# eightbyeight.net
KiCad netlist of a schematic drawn in EAGLE
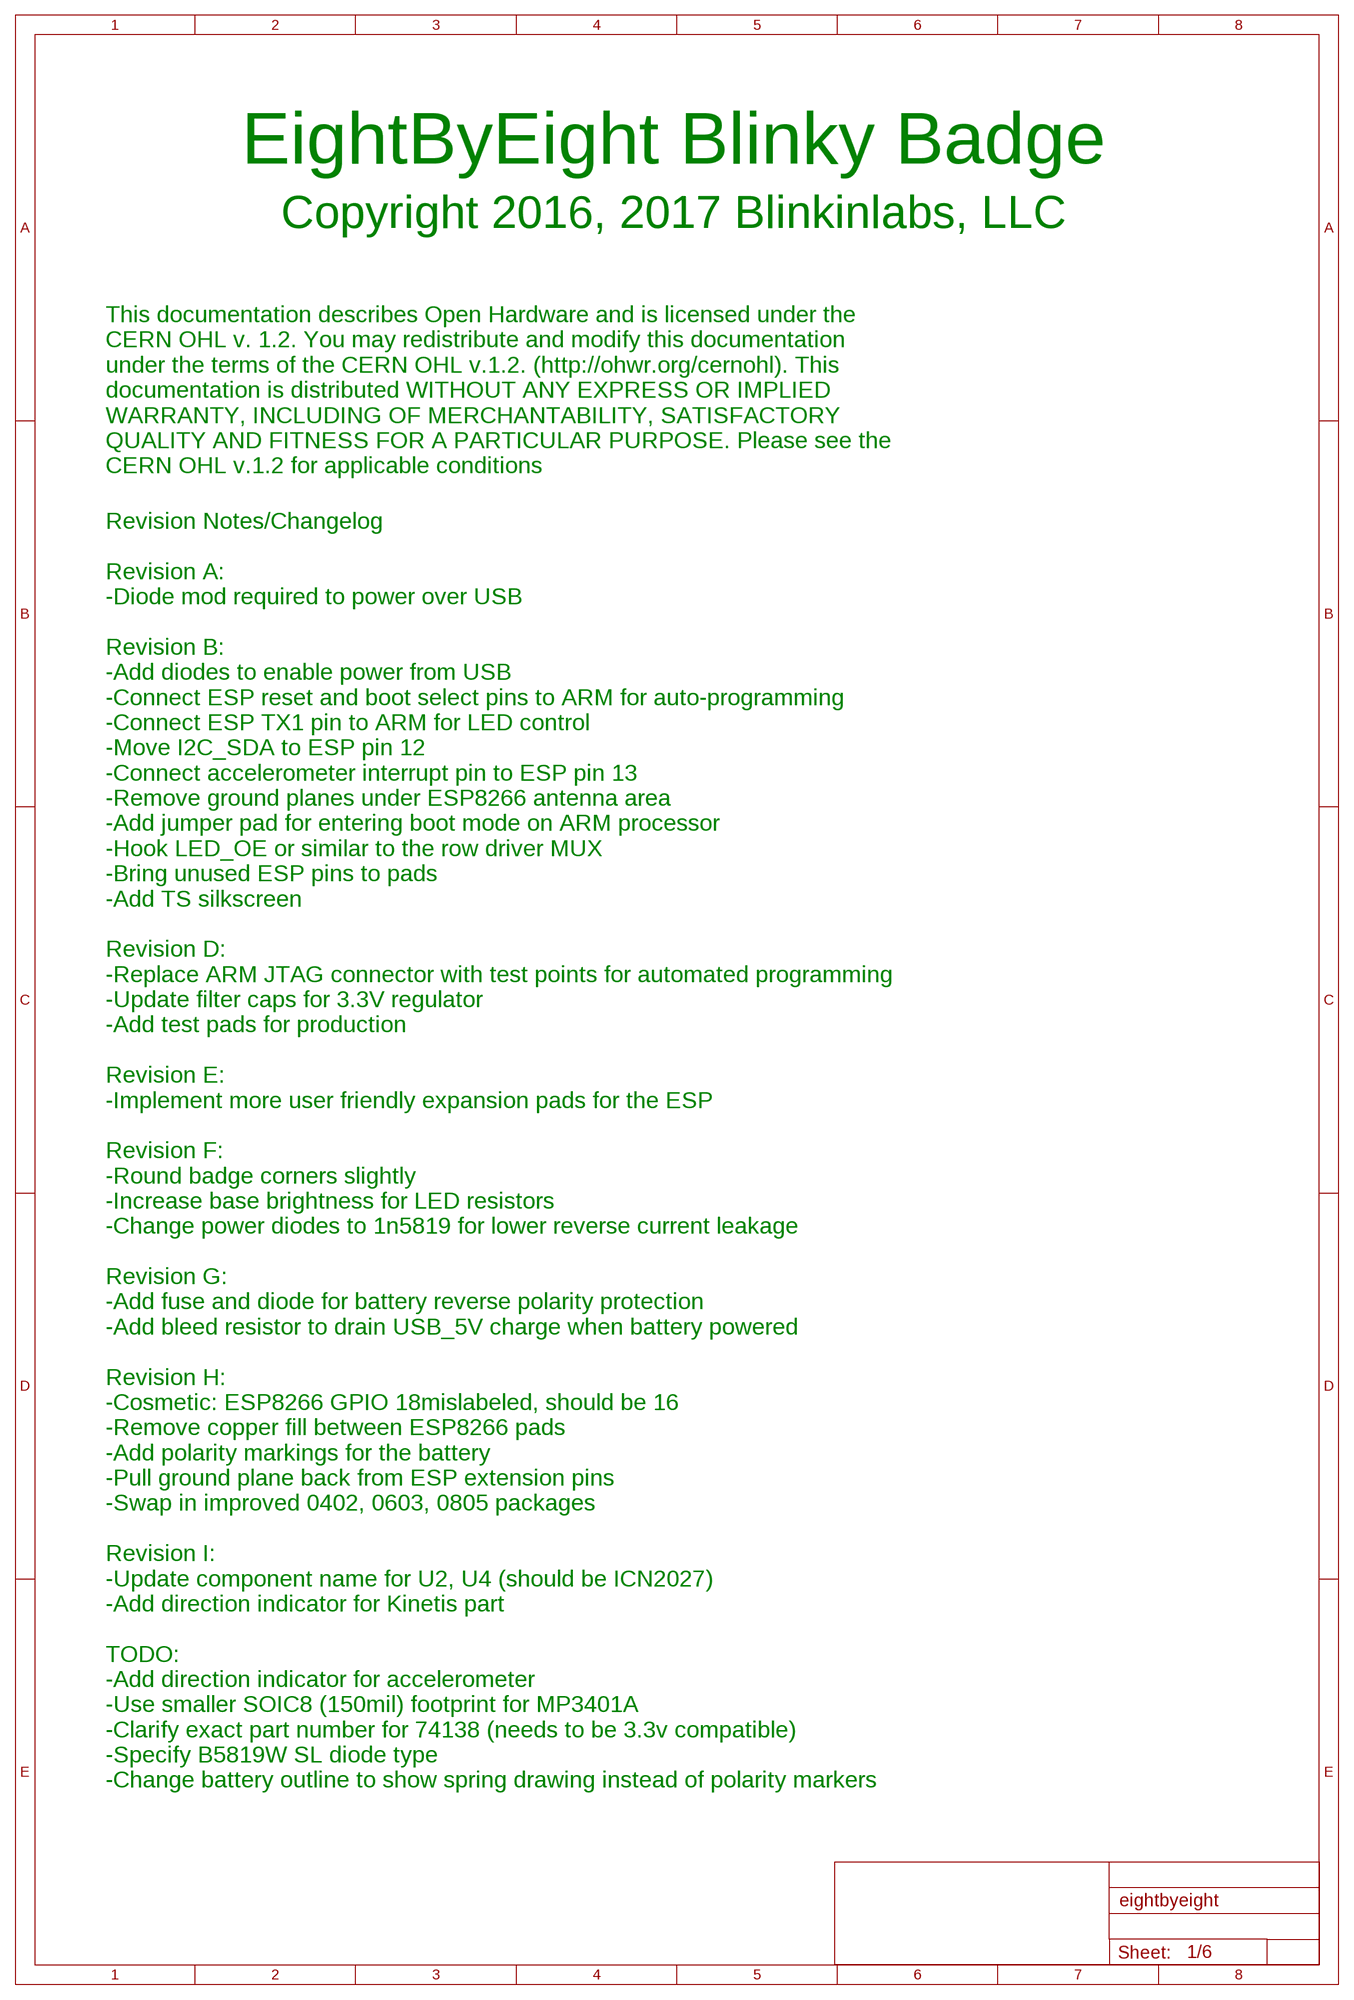
[diagram p0: schematic, sheet 1]
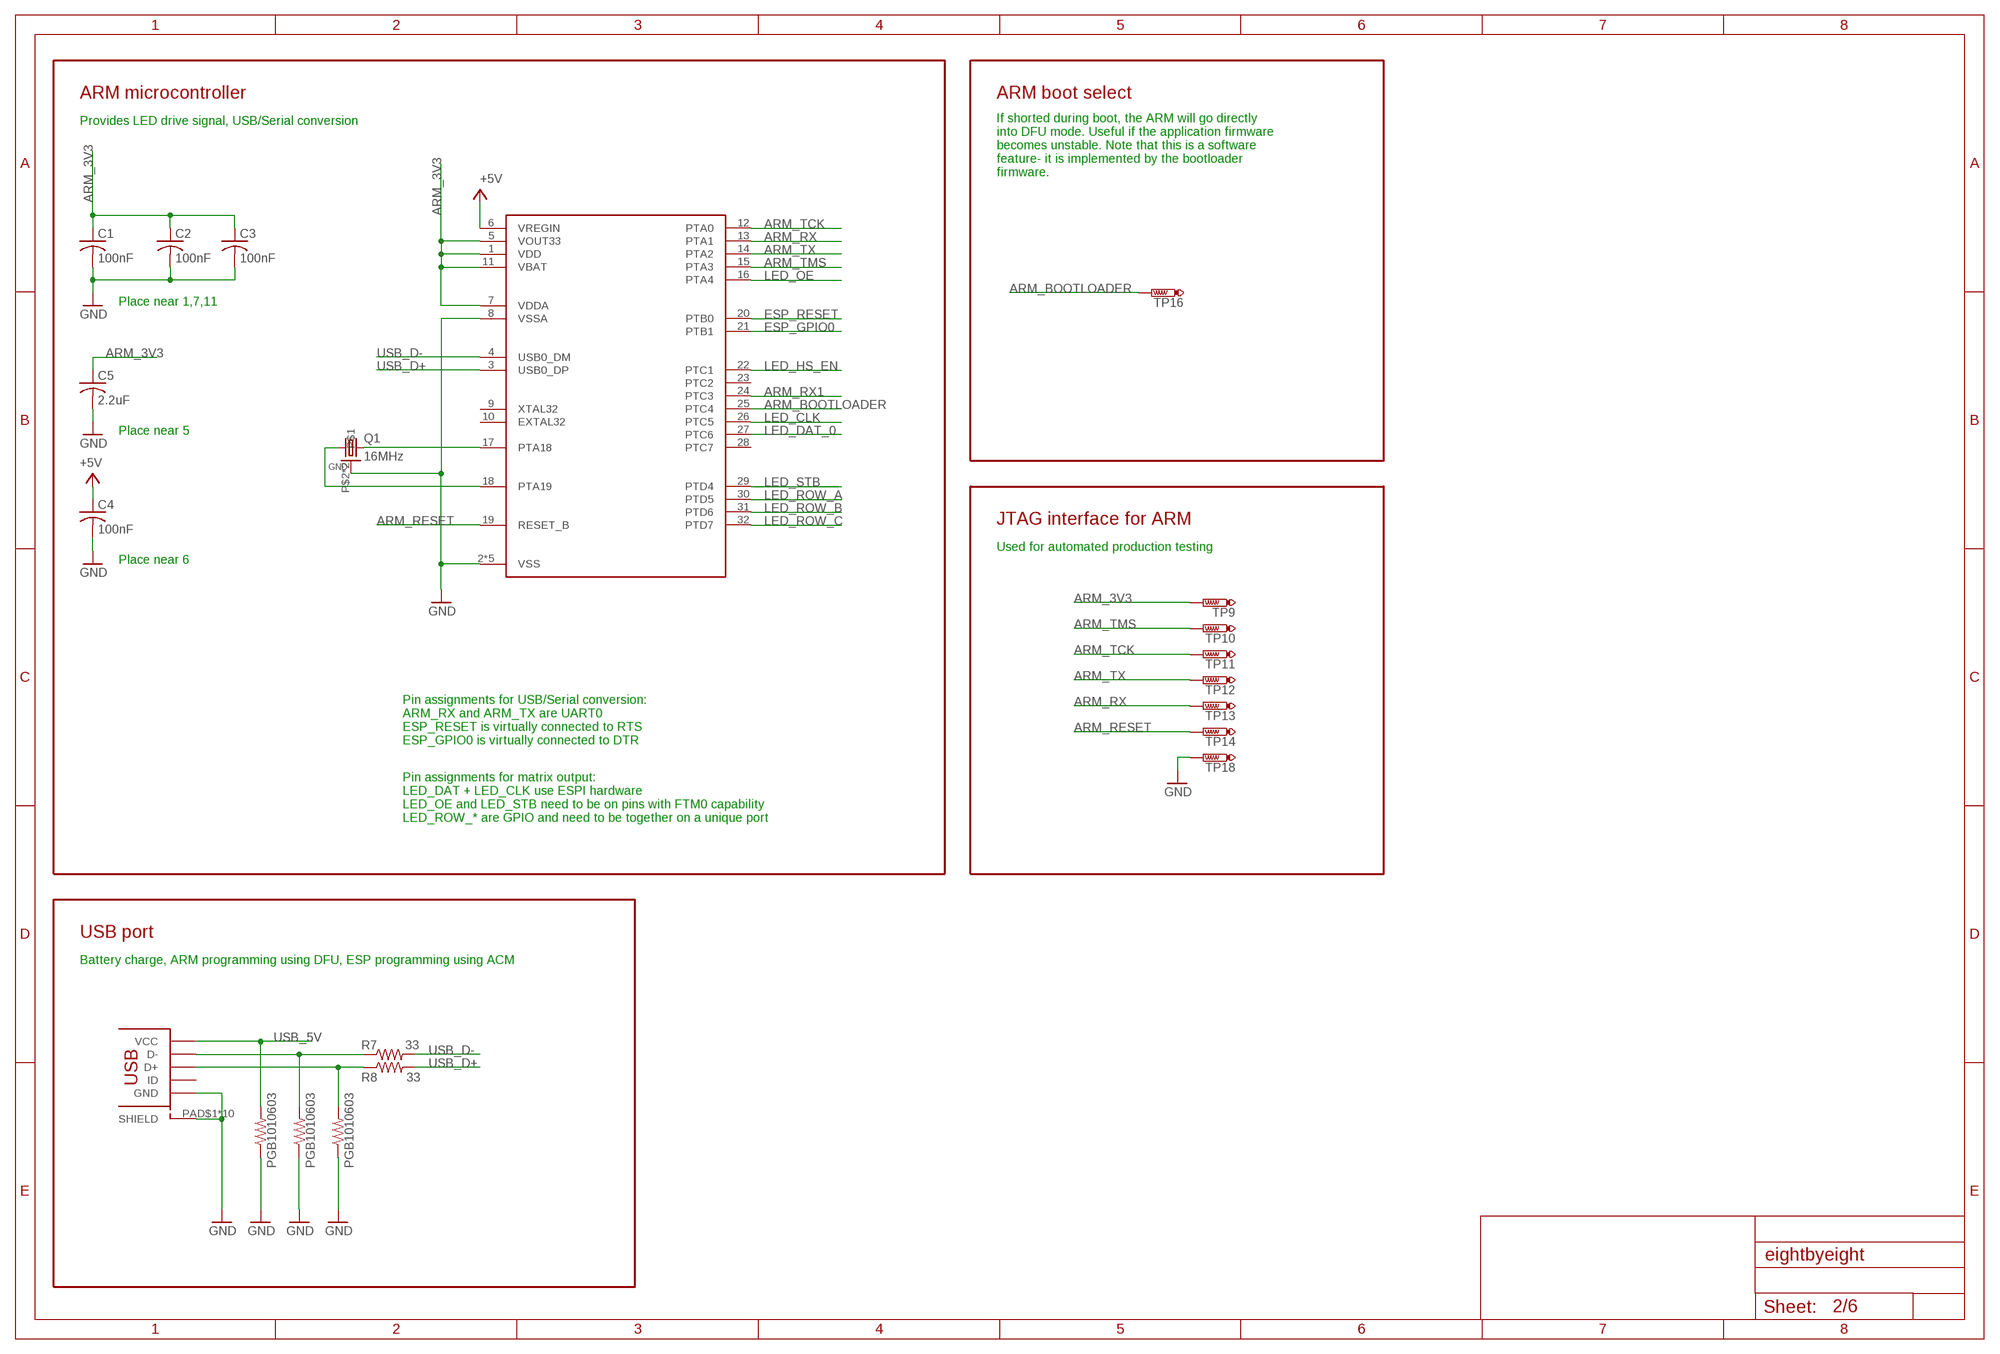
[diagram p1: schematic, sheet 2]
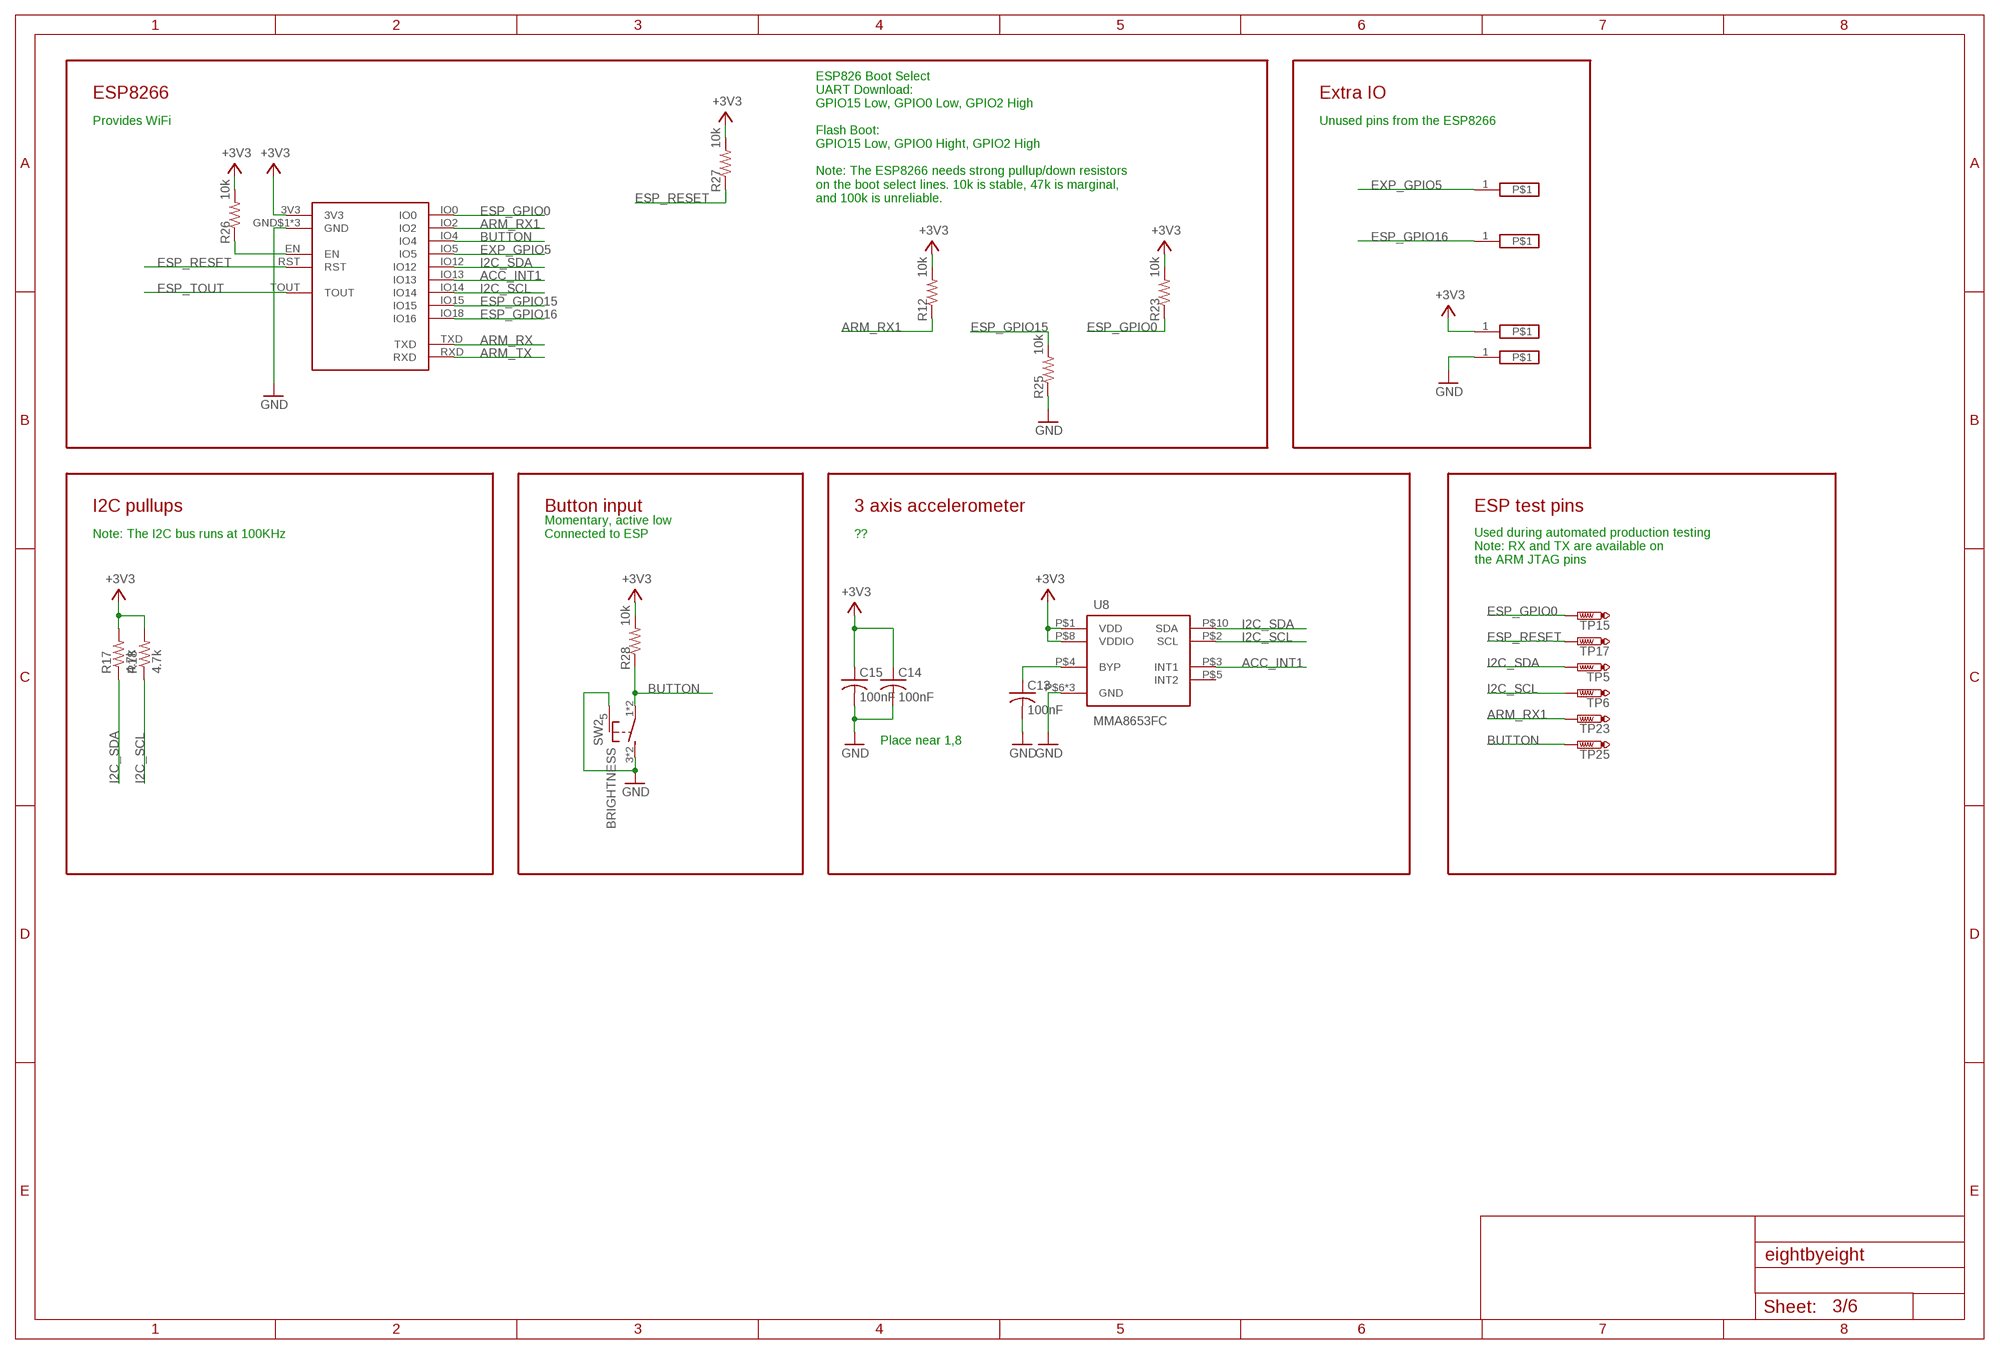
[diagram p2: schematic, sheet 3]
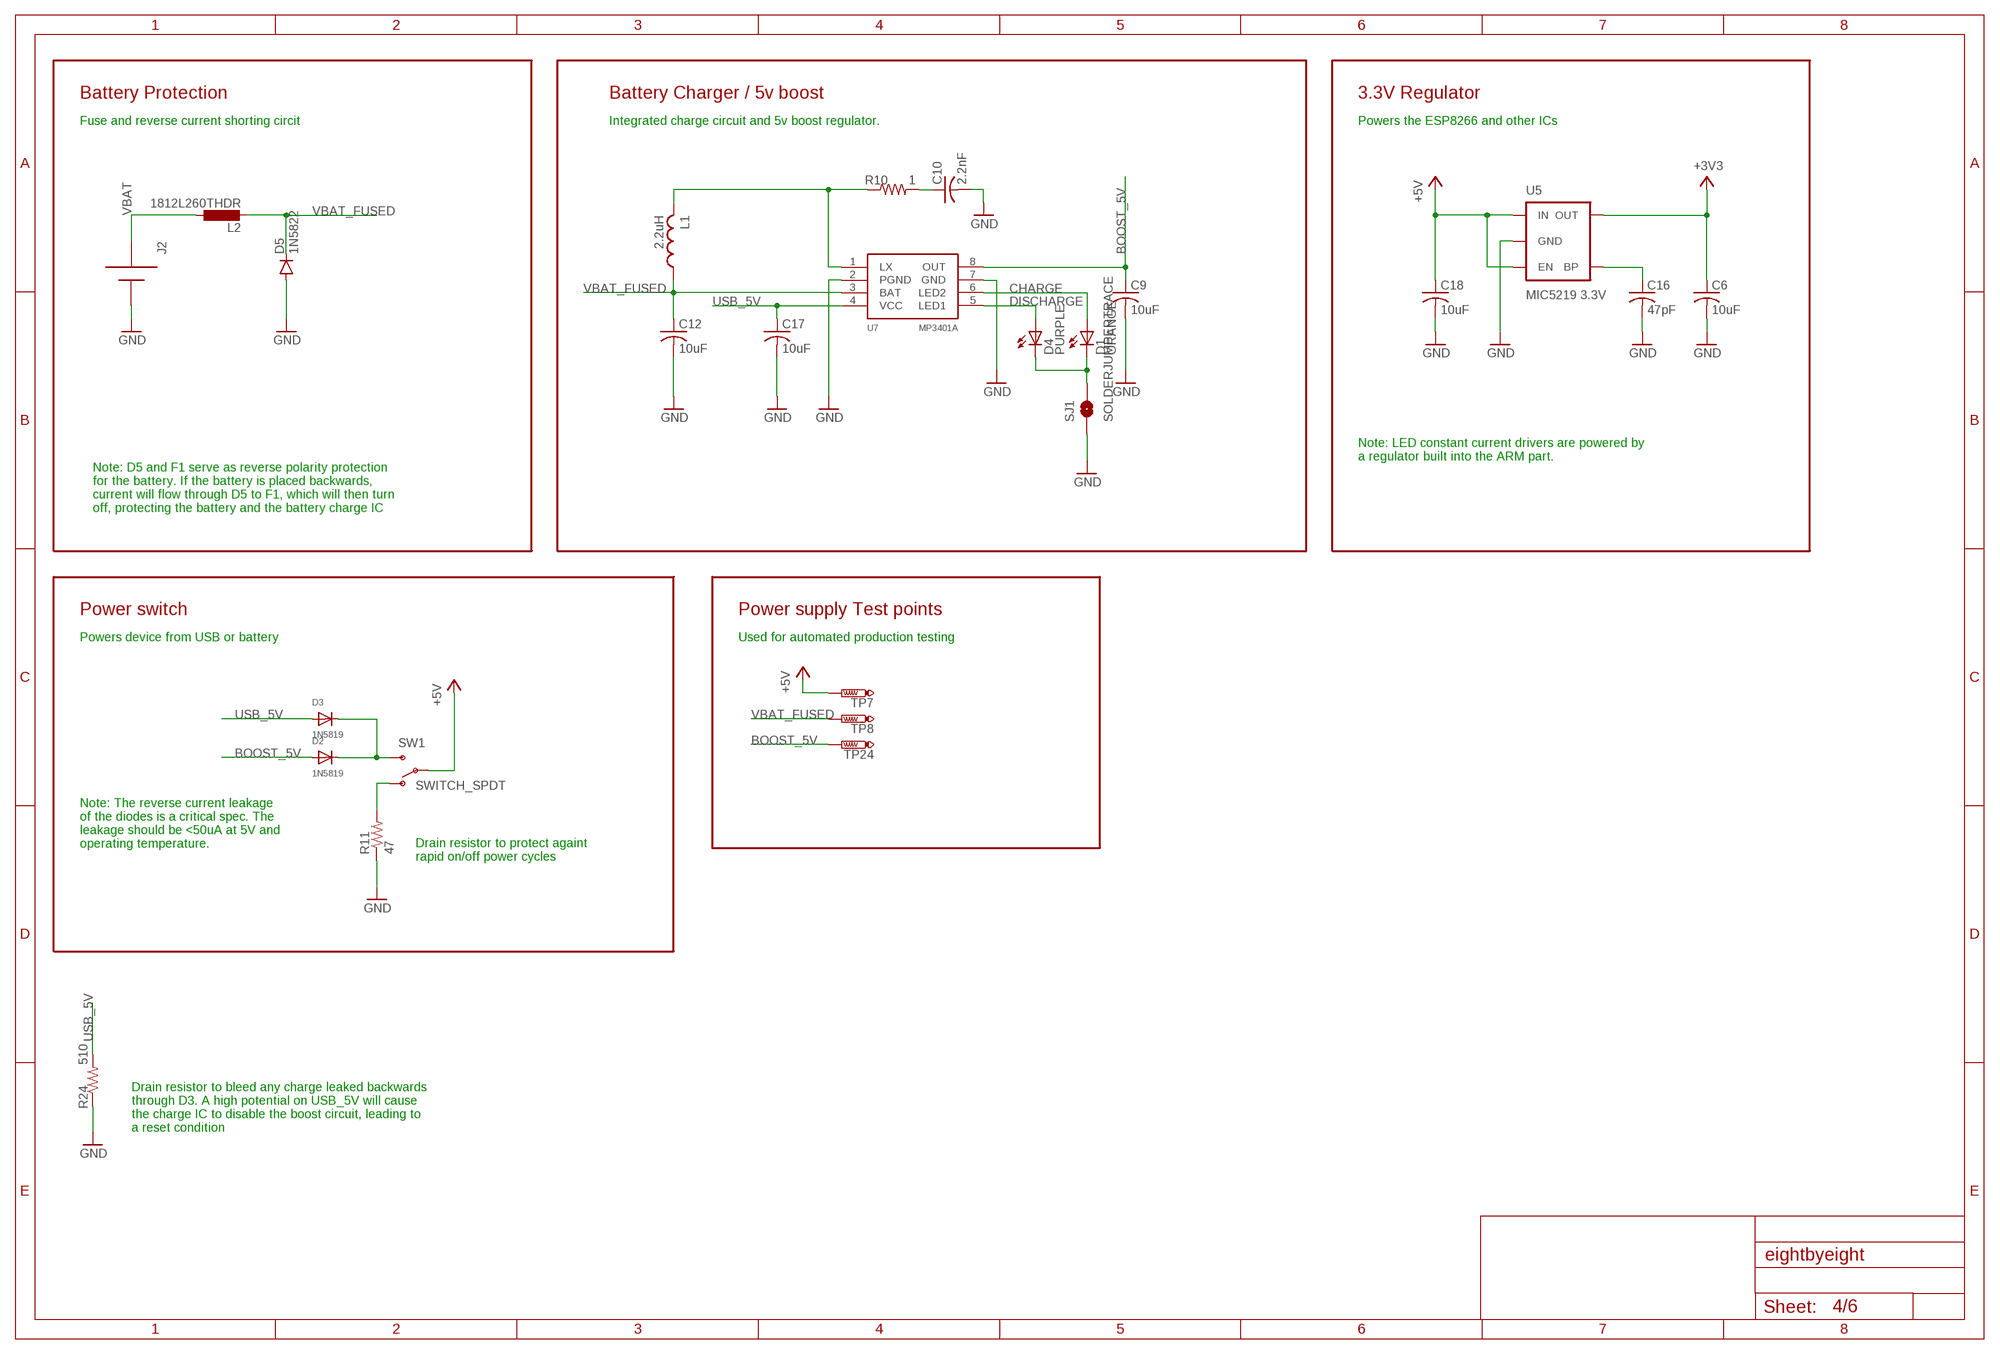
[diagram p3: schematic, sheet 4]
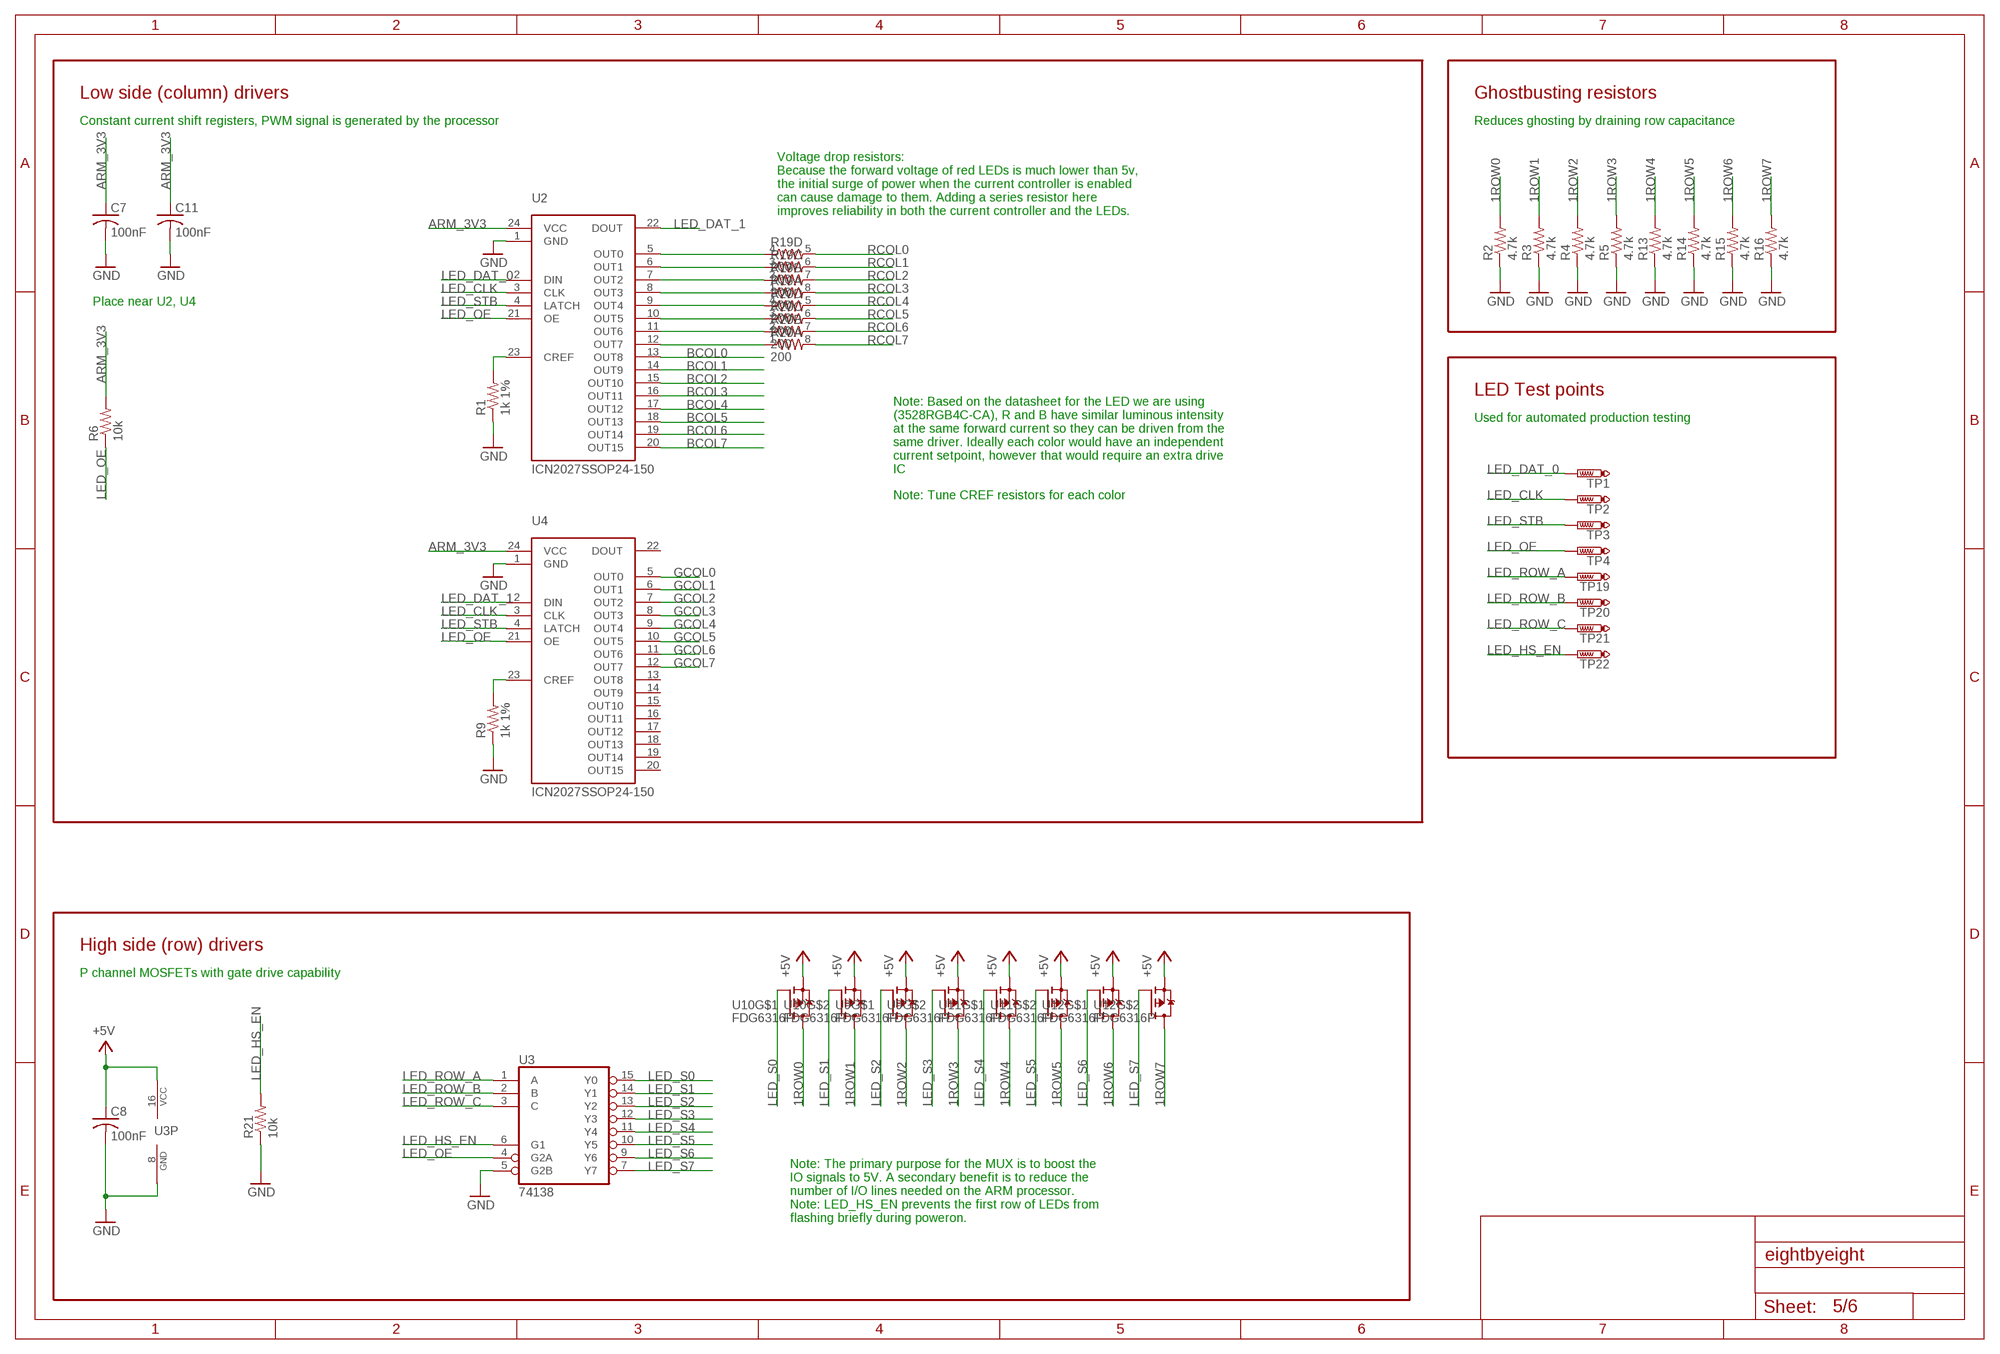
[diagram p4: schematic, sheet 5]
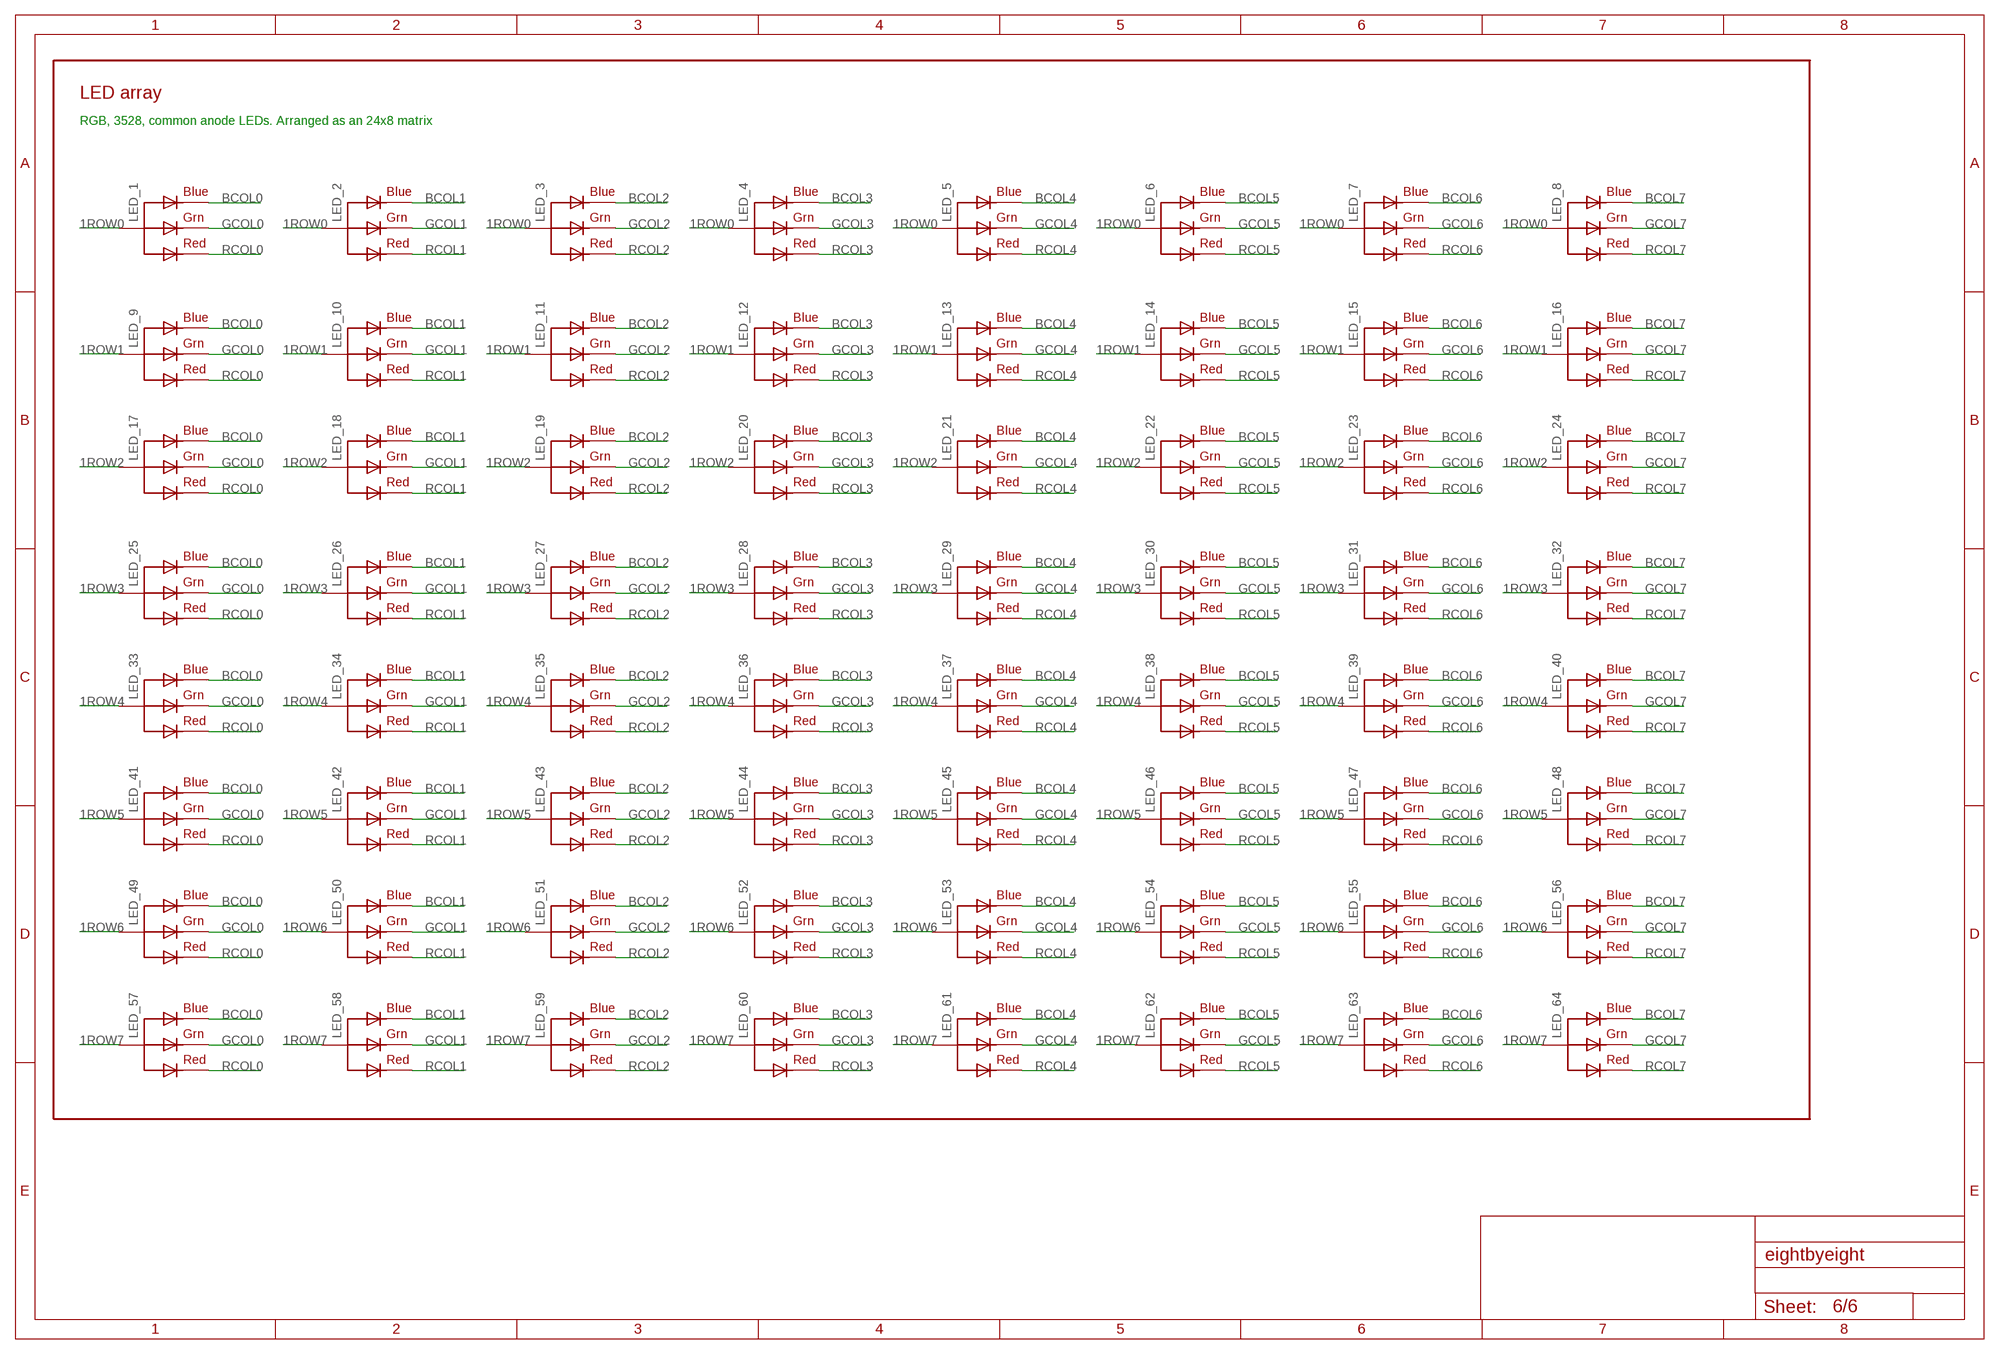
[diagram p5: schematic, sheet 6]

(export (version "E")
  (design (tool "Eeschema 10.0.6"))
  (components
    (comp (ref "C7")
      (value "100nF")
      (footprint "eagle-import:CAP_0402")
      (libsource (lib "eagle-import") (part "C_US0402"))
    )
    (comp (ref "C8")
      (value "100nF")
      (footprint "eagle-import:CAP_0402")
      (libsource (lib "eagle-import") (part "C_US0402"))
    )
    (comp (ref "C11")
      (value "100nF")
      (footprint "eagle-import:CAP_0402")
      (libsource (lib "eagle-import") (part "C_US0402"))
    )
    (comp (ref "R1")
      (value "1k 1%")
      (footprint "eagle-import:R_0402")
      (libsource (lib "eagle-import") (part "R_US0402"))
    )
    (comp (ref "R2")
      (value "4.7k")
      (footprint "eagle-import:R_0402")
      (libsource (lib "eagle-import") (part "R_US0402"))
    )
    (comp (ref "R3")
      (value "4.7k")
      (footprint "eagle-import:R_0402")
      (libsource (lib "eagle-import") (part "R_US0402"))
    )
    (comp (ref "R4")
      (value "4.7k")
      (footprint "eagle-import:R_0402")
      (libsource (lib "eagle-import") (part "R_US0402"))
    )
    (comp (ref "R5")
      (value "4.7k")
      (footprint "eagle-import:R_0402")
      (libsource (lib "eagle-import") (part "R_US0402"))
    )
    (comp (ref "R6")
      (value "10k")
      (footprint "eagle-import:R_0402")
      (libsource (lib "eagle-import") (part "R_US0402"))
    )
    (comp (ref "R9")
      (value "1k 1%")
      (footprint "eagle-import:R_0402")
      (libsource (lib "eagle-import") (part "R_US0402"))
    )
    (comp (ref "R13")
      (value "4.7k")
      (footprint "eagle-import:R_0402")
      (libsource (lib "eagle-import") (part "R_US0402"))
    )
    (comp (ref "R14")
      (value "4.7k")
      (footprint "eagle-import:R_0402")
      (libsource (lib "eagle-import") (part "R_US0402"))
    )
    (comp (ref "R15")
      (value "4.7k")
      (footprint "eagle-import:R_0402")
      (libsource (lib "eagle-import") (part "R_US0402"))
    )
    (comp (ref "R16")
      (value "4.7k")
      (footprint "eagle-import:R_0402")
      (libsource (lib "eagle-import") (part "R_US0402"))
    )
    (comp (ref "R19")
      (value "200")
      (footprint "eagle-import:0603-ARV")
      (libsource (lib "eagle-import") (part "RESISTOR-ARRAY0603-ARV"))
    )
    (comp (ref "R20")
      (value "200")
      (footprint "eagle-import:0603-ARV")
      (libsource (lib "eagle-import") (part "RESISTOR-ARRAY0603-ARV"))
    )
    (comp (ref "R21")
      (value "10k")
      (footprint "eagle-import:R_0402")
      (libsource (lib "eagle-import") (part "R_US0402"))
    )
    (comp (ref "TP1")
      (value "PTR1B1,27")
      (footprint "eagle-import:B1,27")
      (libsource (lib "eagle-import") (part "PTR1B1,27"))
    )
    (comp (ref "TP2")
      (value "PTR1B1,27")
      (footprint "eagle-import:B1,27")
      (libsource (lib "eagle-import") (part "PTR1B1,27"))
    )
    (comp (ref "TP3")
      (value "PTR1B1,27")
      (footprint "eagle-import:B1,27")
      (libsource (lib "eagle-import") (part "PTR1B1,27"))
    )
    (comp (ref "TP4")
      (value "PTR1B1,27")
      (footprint "eagle-import:B1,27")
      (libsource (lib "eagle-import") (part "PTR1B1,27"))
    )
    (comp (ref "TP19")
      (value "PTR1B1,27")
      (footprint "eagle-import:B1,27")
      (libsource (lib "eagle-import") (part "PTR1B1,27"))
    )
    (comp (ref "TP20")
      (value "PTR1B1,27")
      (footprint "eagle-import:B1,27")
      (libsource (lib "eagle-import") (part "PTR1B1,27"))
    )
    (comp (ref "TP21")
      (value "PTR1B1,27")
      (footprint "eagle-import:B1,27")
      (libsource (lib "eagle-import") (part "PTR1B1,27"))
    )
    (comp (ref "TP22")
      (value "PTR1B1,27")
      (footprint "eagle-import:B1,27")
      (libsource (lib "eagle-import") (part "PTR1B1,27"))
    )
    (comp (ref "U2")
      (value "ICN2027SSOP24-150")
      (footprint "eagle-import:SSOP24-150")
      (libsource (lib "eagle-import") (part "ICN2027SSOP24-150"))
    )
    (comp (ref "U3")
      (value "74138")
      (footprint "eagle-import:TSSOP16")
      (libsource (lib "eagle-import") (part "74138"))
    )
    (comp (ref "U4")
      (value "ICN2027SSOP24-150")
      (footprint "eagle-import:SSOP24-150")
      (libsource (lib "eagle-import") (part "ICN2027SSOP24-150"))
    )
    (comp (ref "U9")
      (value "FDG6316P")
      (footprint "eagle-import:SC70-6L")
      (libsource (lib "eagle-import") (part "FDG6316P"))
    )
    (comp (ref "U10")
      (value "FDG6316P")
      (footprint "eagle-import:SC70-6L")
      (libsource (lib "eagle-import") (part "FDG6316P"))
    )
    (comp (ref "U11")
      (value "FDG6316P")
      (footprint "eagle-import:SC70-6L")
      (libsource (lib "eagle-import") (part "FDG6316P"))
    )
    (comp (ref "U12")
      (value "FDG6316P")
      (footprint "eagle-import:SC70-6L")
      (libsource (lib "eagle-import") (part "FDG6316P"))
    )
    (comp (ref "LED_1")
      (value "LED_RGB_CA3528")
      (footprint "eagle-import:LED_3528")
      (libsource (lib "eagle-import") (part "LED_RGB_CA3528"))
    )
    (comp (ref "LED_2")
      (value "LED_RGB_CA3528")
      (footprint "eagle-import:LED_3528")
      (libsource (lib "eagle-import") (part "LED_RGB_CA3528"))
    )
    (comp (ref "LED_3")
      (value "LED_RGB_CA3528")
      (footprint "eagle-import:LED_3528")
      (libsource (lib "eagle-import") (part "LED_RGB_CA3528"))
    )
    (comp (ref "LED_4")
      (value "LED_RGB_CA3528")
      (footprint "eagle-import:LED_3528")
      (libsource (lib "eagle-import") (part "LED_RGB_CA3528"))
    )
    (comp (ref "LED_5")
      (value "LED_RGB_CA3528")
      (footprint "eagle-import:LED_3528")
      (libsource (lib "eagle-import") (part "LED_RGB_CA3528"))
    )
    (comp (ref "LED_6")
      (value "LED_RGB_CA3528")
      (footprint "eagle-import:LED_3528")
      (libsource (lib "eagle-import") (part "LED_RGB_CA3528"))
    )
    (comp (ref "LED_7")
      (value "LED_RGB_CA3528")
      (footprint "eagle-import:LED_3528")
      (libsource (lib "eagle-import") (part "LED_RGB_CA3528"))
    )
    (comp (ref "LED_8")
      (value "LED_RGB_CA3528")
      (footprint "eagle-import:LED_3528")
      (libsource (lib "eagle-import") (part "LED_RGB_CA3528"))
    )
    (comp (ref "LED_9")
      (value "LED_RGB_CA3528")
      (footprint "eagle-import:LED_3528")
      (libsource (lib "eagle-import") (part "LED_RGB_CA3528"))
    )
    (comp (ref "LED_10")
      (value "LED_RGB_CA3528")
      (footprint "eagle-import:LED_3528")
      (libsource (lib "eagle-import") (part "LED_RGB_CA3528"))
    )
    (comp (ref "LED_11")
      (value "LED_RGB_CA3528")
      (footprint "eagle-import:LED_3528")
      (libsource (lib "eagle-import") (part "LED_RGB_CA3528"))
    )
    (comp (ref "LED_12")
      (value "LED_RGB_CA3528")
      (footprint "eagle-import:LED_3528")
      (libsource (lib "eagle-import") (part "LED_RGB_CA3528"))
    )
    (comp (ref "LED_13")
      (value "LED_RGB_CA3528")
      (footprint "eagle-import:LED_3528")
      (libsource (lib "eagle-import") (part "LED_RGB_CA3528"))
    )
    (comp (ref "LED_14")
      (value "LED_RGB_CA3528")
      (footprint "eagle-import:LED_3528")
      (libsource (lib "eagle-import") (part "LED_RGB_CA3528"))
    )
    (comp (ref "LED_15")
      (value "LED_RGB_CA3528")
      (footprint "eagle-import:LED_3528")
      (libsource (lib "eagle-import") (part "LED_RGB_CA3528"))
    )
    (comp (ref "LED_16")
      (value "LED_RGB_CA3528")
      (footprint "eagle-import:LED_3528")
      (libsource (lib "eagle-import") (part "LED_RGB_CA3528"))
    )
    (comp (ref "LED_17")
      (value "LED_RGB_CA3528")
      (footprint "eagle-import:LED_3528")
      (libsource (lib "eagle-import") (part "LED_RGB_CA3528"))
    )
    (comp (ref "LED_18")
      (value "LED_RGB_CA3528")
      (footprint "eagle-import:LED_3528")
      (libsource (lib "eagle-import") (part "LED_RGB_CA3528"))
    )
    (comp (ref "LED_19")
      (value "LED_RGB_CA3528")
      (footprint "eagle-import:LED_3528")
      (libsource (lib "eagle-import") (part "LED_RGB_CA3528"))
    )
    (comp (ref "LED_20")
      (value "LED_RGB_CA3528")
      (footprint "eagle-import:LED_3528")
      (libsource (lib "eagle-import") (part "LED_RGB_CA3528"))
    )
    (comp (ref "LED_21")
      (value "LED_RGB_CA3528")
      (footprint "eagle-import:LED_3528")
      (libsource (lib "eagle-import") (part "LED_RGB_CA3528"))
    )
    (comp (ref "LED_22")
      (value "LED_RGB_CA3528")
      (footprint "eagle-import:LED_3528")
      (libsource (lib "eagle-import") (part "LED_RGB_CA3528"))
    )
    (comp (ref "LED_23")
      (value "LED_RGB_CA3528")
      (footprint "eagle-import:LED_3528")
      (libsource (lib "eagle-import") (part "LED_RGB_CA3528"))
    )
    (comp (ref "LED_24")
      (value "LED_RGB_CA3528")
      (footprint "eagle-import:LED_3528")
      (libsource (lib "eagle-import") (part "LED_RGB_CA3528"))
    )
    (comp (ref "LED_25")
      (value "LED_RGB_CA3528")
      (footprint "eagle-import:LED_3528")
      (libsource (lib "eagle-import") (part "LED_RGB_CA3528"))
    )
    (comp (ref "LED_26")
      (value "LED_RGB_CA3528")
      (footprint "eagle-import:LED_3528")
      (libsource (lib "eagle-import") (part "LED_RGB_CA3528"))
    )
    (comp (ref "LED_27")
      (value "LED_RGB_CA3528")
      (footprint "eagle-import:LED_3528")
      (libsource (lib "eagle-import") (part "LED_RGB_CA3528"))
    )
    (comp (ref "LED_28")
      (value "LED_RGB_CA3528")
      (footprint "eagle-import:LED_3528")
      (libsource (lib "eagle-import") (part "LED_RGB_CA3528"))
    )
    (comp (ref "LED_29")
      (value "LED_RGB_CA3528")
      (footprint "eagle-import:LED_3528")
      (libsource (lib "eagle-import") (part "LED_RGB_CA3528"))
    )
    (comp (ref "LED_30")
      (value "LED_RGB_CA3528")
      (footprint "eagle-import:LED_3528")
      (libsource (lib "eagle-import") (part "LED_RGB_CA3528"))
    )
    (comp (ref "LED_31")
      (value "LED_RGB_CA3528")
      (footprint "eagle-import:LED_3528")
      (libsource (lib "eagle-import") (part "LED_RGB_CA3528"))
    )
    (comp (ref "LED_32")
      (value "LED_RGB_CA3528")
      (footprint "eagle-import:LED_3528")
      (libsource (lib "eagle-import") (part "LED_RGB_CA3528"))
    )
    (comp (ref "LED_33")
      (value "LED_RGB_CA3528")
      (footprint "eagle-import:LED_3528")
      (libsource (lib "eagle-import") (part "LED_RGB_CA3528"))
    )
    (comp (ref "LED_34")
      (value "LED_RGB_CA3528")
      (footprint "eagle-import:LED_3528")
      (libsource (lib "eagle-import") (part "LED_RGB_CA3528"))
    )
    (comp (ref "LED_35")
      (value "LED_RGB_CA3528")
      (footprint "eagle-import:LED_3528")
      (libsource (lib "eagle-import") (part "LED_RGB_CA3528"))
    )
    (comp (ref "LED_36")
      (value "LED_RGB_CA3528")
      (footprint "eagle-import:LED_3528")
      (libsource (lib "eagle-import") (part "LED_RGB_CA3528"))
    )
    (comp (ref "LED_37")
      (value "LED_RGB_CA3528")
      (footprint "eagle-import:LED_3528")
      (libsource (lib "eagle-import") (part "LED_RGB_CA3528"))
    )
    (comp (ref "LED_38")
      (value "LED_RGB_CA3528")
      (footprint "eagle-import:LED_3528")
      (libsource (lib "eagle-import") (part "LED_RGB_CA3528"))
    )
    (comp (ref "LED_39")
      (value "LED_RGB_CA3528")
      (footprint "eagle-import:LED_3528")
      (libsource (lib "eagle-import") (part "LED_RGB_CA3528"))
    )
    (comp (ref "LED_40")
      (value "LED_RGB_CA3528")
      (footprint "eagle-import:LED_3528")
      (libsource (lib "eagle-import") (part "LED_RGB_CA3528"))
    )
    (comp (ref "LED_41")
      (value "LED_RGB_CA3528")
      (footprint "eagle-import:LED_3528")
      (libsource (lib "eagle-import") (part "LED_RGB_CA3528"))
    )
    (comp (ref "LED_42")
      (value "LED_RGB_CA3528")
      (footprint "eagle-import:LED_3528")
      (libsource (lib "eagle-import") (part "LED_RGB_CA3528"))
    )
    (comp (ref "LED_43")
      (value "LED_RGB_CA3528")
      (footprint "eagle-import:LED_3528")
      (libsource (lib "eagle-import") (part "LED_RGB_CA3528"))
    )
    (comp (ref "LED_44")
      (value "LED_RGB_CA3528")
      (footprint "eagle-import:LED_3528")
      (libsource (lib "eagle-import") (part "LED_RGB_CA3528"))
    )
    (comp (ref "LED_45")
      (value "LED_RGB_CA3528")
      (footprint "eagle-import:LED_3528")
      (libsource (lib "eagle-import") (part "LED_RGB_CA3528"))
    )
    (comp (ref "LED_46")
      (value "LED_RGB_CA3528")
      (footprint "eagle-import:LED_3528")
      (libsource (lib "eagle-import") (part "LED_RGB_CA3528"))
    )
    (comp (ref "LED_47")
      (value "LED_RGB_CA3528")
      (footprint "eagle-import:LED_3528")
      (libsource (lib "eagle-import") (part "LED_RGB_CA3528"))
    )
    (comp (ref "LED_48")
      (value "LED_RGB_CA3528")
      (footprint "eagle-import:LED_3528")
      (libsource (lib "eagle-import") (part "LED_RGB_CA3528"))
    )
    (comp (ref "LED_49")
      (value "LED_RGB_CA3528")
      (footprint "eagle-import:LED_3528")
      (libsource (lib "eagle-import") (part "LED_RGB_CA3528"))
    )
    (comp (ref "LED_50")
      (value "LED_RGB_CA3528")
      (footprint "eagle-import:LED_3528")
      (libsource (lib "eagle-import") (part "LED_RGB_CA3528"))
    )
    (comp (ref "LED_51")
      (value "LED_RGB_CA3528")
      (footprint "eagle-import:LED_3528")
      (libsource (lib "eagle-import") (part "LED_RGB_CA3528"))
    )
    (comp (ref "LED_52")
      (value "LED_RGB_CA3528")
      (footprint "eagle-import:LED_3528")
      (libsource (lib "eagle-import") (part "LED_RGB_CA3528"))
    )
    (comp (ref "LED_53")
      (value "LED_RGB_CA3528")
      (footprint "eagle-import:LED_3528")
      (libsource (lib "eagle-import") (part "LED_RGB_CA3528"))
    )
    (comp (ref "LED_54")
      (value "LED_RGB_CA3528")
      (footprint "eagle-import:LED_3528")
      (libsource (lib "eagle-import") (part "LED_RGB_CA3528"))
    )
    (comp (ref "LED_55")
      (value "LED_RGB_CA3528")
      (footprint "eagle-import:LED_3528")
      (libsource (lib "eagle-import") (part "LED_RGB_CA3528"))
    )
    (comp (ref "LED_56")
      (value "LED_RGB_CA3528")
      (footprint "eagle-import:LED_3528")
      (libsource (lib "eagle-import") (part "LED_RGB_CA3528"))
    )
    (comp (ref "LED_57")
      (value "LED_RGB_CA3528")
      (footprint "eagle-import:LED_3528")
      (libsource (lib "eagle-import") (part "LED_RGB_CA3528"))
    )
    (comp (ref "LED_58")
      (value "LED_RGB_CA3528")
      (footprint "eagle-import:LED_3528")
      (libsource (lib "eagle-import") (part "LED_RGB_CA3528"))
    )
    (comp (ref "LED_59")
      (value "LED_RGB_CA3528")
      (footprint "eagle-import:LED_3528")
      (libsource (lib "eagle-import") (part "LED_RGB_CA3528"))
    )
    (comp (ref "LED_60")
      (value "LED_RGB_CA3528")
      (footprint "eagle-import:LED_3528")
      (libsource (lib "eagle-import") (part "LED_RGB_CA3528"))
    )
    (comp (ref "LED_61")
      (value "LED_RGB_CA3528")
      (footprint "eagle-import:LED_3528")
      (libsource (lib "eagle-import") (part "LED_RGB_CA3528"))
    )
    (comp (ref "LED_62")
      (value "LED_RGB_CA3528")
      (footprint "eagle-import:LED_3528")
      (libsource (lib "eagle-import") (part "LED_RGB_CA3528"))
    )
    (comp (ref "LED_63")
      (value "LED_RGB_CA3528")
      (footprint "eagle-import:LED_3528")
      (libsource (lib "eagle-import") (part "LED_RGB_CA3528"))
    )
    (comp (ref "LED_64")
      (value "LED_RGB_CA3528")
      (footprint "eagle-import:LED_3528")
      (libsource (lib "eagle-import") (part "LED_RGB_CA3528"))
    )
    (comp (ref "C13")
      (value "100nF")
      (footprint "eagle-import:CAP_0402")
      (libsource (lib "eagle-import") (part "C_US0402"))
    )
    (comp (ref "C14")
      (value "100nF")
      (footprint "eagle-import:CAP_0402")
      (libsource (lib "eagle-import") (part "C_US0402"))
    )
    (comp (ref "C15")
      (value "100nF")
      (footprint "eagle-import:CAP_0402")
      (libsource (lib "eagle-import") (part "C_US0402"))
    )
    (comp (ref "R12")
      (value "10k")
      (footprint "eagle-import:R_0402")
      (libsource (lib "eagle-import") (part "R_US0402"))
    )
    (comp (ref "R17")
      (value "4.7k")
      (footprint "eagle-import:R_0402")
      (libsource (lib "eagle-import") (part "R_US0402"))
    )
    (comp (ref "R18")
      (value "4.7k")
      (footprint "eagle-import:R_0402")
      (libsource (lib "eagle-import") (part "R_US0402"))
    )
    (comp (ref "R23")
      (value "10k")
      (footprint "eagle-import:R_0402")
      (libsource (lib "eagle-import") (part "R_US0402"))
    )
    (comp (ref "R25")
      (value "10k")
      (footprint "eagle-import:R_0402")
      (libsource (lib "eagle-import") (part "R_US0402"))
    )
    (comp (ref "R26")
      (value "10k")
      (footprint "eagle-import:R_0402")
      (libsource (lib "eagle-import") (part "R_US0402"))
    )
    (comp (ref "R27")
      (value "10k")
      (footprint "eagle-import:R_0402")
      (libsource (lib "eagle-import") (part "R_US0402"))
    )
    (comp (ref "R28")
      (value "10k")
      (footprint "eagle-import:R_0402")
      (libsource (lib "eagle-import") (part "R_US0402"))
    )
    (comp (ref "SW2")
      (value "BRIGHTNESS")
      (footprint "eagle-import:TD-07XB")
      (libsource (lib "eagle-import") (part "BUTTON_MOMENTARY_GROUNDTD-07XB"))
    )
    (comp (ref "TP5")
      (value "PTR1B1,27")
      (footprint "eagle-import:B1,27")
      (libsource (lib "eagle-import") (part "PTR1B1,27"))
    )
    (comp (ref "TP6")
      (value "PTR1B1,27")
      (footprint "eagle-import:B1,27")
      (libsource (lib "eagle-import") (part "PTR1B1,27"))
    )
    (comp (ref "TP15")
      (value "PTR1B1,27")
      (footprint "eagle-import:B1,27")
      (libsource (lib "eagle-import") (part "PTR1B1,27"))
    )
    (comp (ref "TP17")
      (value "PTR1B1,27")
      (footprint "eagle-import:B1,27")
      (libsource (lib "eagle-import") (part "PTR1B1,27"))
    )
    (comp (ref "TP23")
      (value "PTR1B1,27")
      (footprint "eagle-import:B1,27")
      (libsource (lib "eagle-import") (part "PTR1B1,27"))
    )
    (comp (ref "TP25")
      (value "PTR1B1,27")
      (footprint "eagle-import:B1,27")
      (libsource (lib "eagle-import") (part "PTR1B1,27"))
    )
    (comp (ref "U$2")
      (value "TEST_POINT")
      (footprint "eagle-import:IO_HOLE_3MM")
      (libsource (lib "eagle-import") (part "TEST_POINT"))
    )
    (comp (ref "U$6")
      (value "TEST_POINT")
      (footprint "eagle-import:IO_HOLE_3MM")
      (libsource (lib "eagle-import") (part "TEST_POINT"))
    )
    (comp (ref "U$9")
      (value "TEST_POINT")
      (footprint "eagle-import:IO_HOLE_3MM")
      (libsource (lib "eagle-import") (part "TEST_POINT"))
    )
    (comp (ref "U$10")
      (value "TEST_POINT")
      (footprint "eagle-import:IO_HOLE_3MM")
      (libsource (lib "eagle-import") (part "TEST_POINT"))
    )
    (comp (ref "U6")
      (value "ESP_WROOM_02")
      (footprint "eagle-import:ESP_WROOM_02")
      (libsource (lib "eagle-import") (part "ESP_WROOM_02"))
    )
    (comp (ref "U8")
      (value "MMA8653FC")
      (footprint "eagle-import:VFDFN-10")
      (libsource (lib "eagle-import") (part "MMA8653FC"))
    )
    (comp (ref "C6")
      (value "10uF")
      (footprint "eagle-import:CAP_0805")
      (libsource (lib "eagle-import") (part "C_US0805"))
    )
    (comp (ref "C9")
      (value "10uF")
      (footprint "eagle-import:CAP_0805")
      (libsource (lib "eagle-import") (part "C_US0805"))
    )
    (comp (ref "C10")
      (value "2.2nF")
      (footprint "eagle-import:CAP_0603")
      (libsource (lib "eagle-import") (part "C_US0603"))
    )
    (comp (ref "C12")
      (value "10uF")
      (footprint "eagle-import:CAP_0805")
      (libsource (lib "eagle-import") (part "C_US0805"))
    )
    (comp (ref "C16")
      (value "47pF")
      (footprint "eagle-import:CAP_0402")
      (libsource (lib "eagle-import") (part "C_US0402"))
    )
    (comp (ref "C17")
      (value "10uF")
      (footprint "eagle-import:CAP_0805")
      (libsource (lib "eagle-import") (part "C_US0805"))
    )
    (comp (ref "C18")
      (value "10uF")
      (footprint "eagle-import:CAP_0805")
      (libsource (lib "eagle-import") (part "C_US0805"))
    )
    (comp (ref "D1")
      (value "ORANGE")
      (footprint "eagle-import:CHIP-LED0603")
      (libsource (lib "eagle-import") (part "LEDCHIP-LED0603"))
    )
    (comp (ref "D2")
      (value "1N5819")
      (footprint "eagle-import:SOD-123")
      (libsource (lib "eagle-import") (part "DIODESOD-123"))
    )
    (comp (ref "D3")
      (value "1N5819")
      (footprint "eagle-import:SOD-123")
      (libsource (lib "eagle-import") (part "DIODESOD-123"))
    )
    (comp (ref "D4")
      (value "PURPLE")
      (footprint "eagle-import:CHIP-LED0603")
      (libsource (lib "eagle-import") (part "LEDCHIP-LED0603"))
    )
    (comp (ref "D5")
      (value "1N5822")
      (footprint "eagle-import:SMA-DIODE")
      (libsource (lib "eagle-import") (part "DIODESMA"))
    )
    (comp (ref "J2")
      (value "BATTERYAA_SMD")
      (footprint "eagle-import:BATTERY_AA_SMD")
      (libsource (lib "eagle-import") (part "BATTERYAA_SMD"))
    )
    (comp (ref "L1")
      (value "2.2uH")
      (footprint "eagle-import:INDUCTOR_CD43")
      (libsource (lib "eagle-import") (part "LCD43"))
    )
    (comp (ref "L2")
      (value "1812L260THDR")
      (footprint "eagle-import:L1812")
      (libsource (lib "eagle-import") (part "L-EUL1812"))
    )
    (comp (ref "R10")
      (value "1")
      (footprint "eagle-import:R_0603")
      (libsource (lib "eagle-import") (part "R_US0603"))
    )
    (comp (ref "R11")
      (value "47")
      (footprint "eagle-import:R_0805")
      (libsource (lib "eagle-import") (part "R_US0805"))
    )
    (comp (ref "R24")
      (value "510")
      (footprint "eagle-import:R_0603")
      (libsource (lib "eagle-import") (part "R_US0603"))
    )
    (comp (ref "SJ1")
      (value "SOLDERJUMPERTRACE")
      (footprint "eagle-import:SJ_2S-TRACE")
      (libsource (lib "eagle-import") (part "SOLDERJUMPERTRACE"))
    )
    (comp (ref "SW1")
      (value "SWITCH_SPDT")
      (footprint "eagle-import:SWITCH_6P-2POS")
      (libsource (lib "eagle-import") (part "SWITCH_SPDT"))
    )
    (comp (ref "TP7")
      (value "PTR1B1,27")
      (footprint "eagle-import:B1,27")
      (libsource (lib "eagle-import") (part "PTR1B1,27"))
    )
    (comp (ref "TP8")
      (value "PTR1B1,27")
      (footprint "eagle-import:B1,27")
      (libsource (lib "eagle-import") (part "PTR1B1,27"))
    )
    (comp (ref "TP24")
      (value "PTR1B1,27")
      (footprint "eagle-import:B1,27")
      (libsource (lib "eagle-import") (part "PTR1B1,27"))
    )
    (comp (ref "U5")
      (value "MIC5219 3.3V")
      (footprint "eagle-import:SOT23-5")
      (libsource (lib "eagle-import") (part "V_REG_MIC52193.3V"))
    )
    (comp (ref "U7")
      (value "MP3401A")
      (footprint "eagle-import:SO08-150")
      (libsource (lib "eagle-import") (part "MP3401A"))
    )
    (comp (ref "C1")
      (value "100nF")
      (footprint "eagle-import:CAP_0402")
      (libsource (lib "eagle-import") (part "C_US0402"))
    )
    (comp (ref "C2")
      (value "100nF")
      (footprint "eagle-import:CAP_0402")
      (libsource (lib "eagle-import") (part "C_US0402"))
    )
    (comp (ref "C3")
      (value "100nF")
      (footprint "eagle-import:CAP_0402")
      (libsource (lib "eagle-import") (part "C_US0402"))
    )
    (comp (ref "C4")
      (value "100nF")
      (footprint "eagle-import:CAP_0402")
      (libsource (lib "eagle-import") (part "C_US0402"))
    )
    (comp (ref "C5")
      (value "2.2uF")
      (footprint "eagle-import:CAP_0402")
      (libsource (lib "eagle-import") (part "C_US0402"))
    )
    (comp (ref "J1")
      (value "USB_MICROSMT+THRUHULE")
      (footprint "eagle-import:USB_MICRO_THRUHOLE")
      (libsource (lib "eagle-import") (part "USB_MICROSMT+THRUHULE"))
    )
    (comp (ref "Q1")
      (value "16MHz")
      (footprint "eagle-import:CRSYTAL_2520")
      (libsource (lib "eagle-import") (part "CRYSTAL_4PAD2520"))
    )
    (comp (ref "R7")
      (value "33")
      (footprint "eagle-import:R_0402")
      (libsource (lib "eagle-import") (part "R_US0402"))
    )
    (comp (ref "R8")
      (value "33")
      (footprint "eagle-import:R_0402")
      (libsource (lib "eagle-import") (part "R_US0402"))
    )
    (comp (ref "TP9")
      (value "PTR1B1,27")
      (footprint "eagle-import:B1,27")
      (libsource (lib "eagle-import") (part "PTR1B1,27"))
    )
    (comp (ref "TP10")
      (value "PTR1B1,27")
      (footprint "eagle-import:B1,27")
      (libsource (lib "eagle-import") (part "PTR1B1,27"))
    )
    (comp (ref "TP11")
      (value "PTR1B1,27")
      (footprint "eagle-import:B1,27")
      (libsource (lib "eagle-import") (part "PTR1B1,27"))
    )
    (comp (ref "TP12")
      (value "PTR1B1,27")
      (footprint "eagle-import:B1,27")
      (libsource (lib "eagle-import") (part "PTR1B1,27"))
    )
    (comp (ref "TP13")
      (value "PTR1B1,27")
      (footprint "eagle-import:B1,27")
      (libsource (lib "eagle-import") (part "PTR1B1,27"))
    )
    (comp (ref "TP14")
      (value "PTR1B1,27")
      (footprint "eagle-import:B1,27")
      (libsource (lib "eagle-import") (part "PTR1B1,27"))
    )
    (comp (ref "TP16")
      (value "PTR1B1,27")
      (footprint "eagle-import:B1,27")
      (libsource (lib "eagle-import") (part "PTR1B1,27"))
    )
    (comp (ref "TP18")
      (value "PTR1B1,27")
      (footprint "eagle-import:B1,27")
      (libsource (lib "eagle-import") (part "PTR1B1,27"))
    )
    (comp (ref "U1")
      (value "MK20DN64VFM5")
      (footprint "eagle-import:QFN32_5X5_LONGLEADS")
      (libsource (lib "eagle-import") (part "MK20D--VFM5"))
    )
    (comp (ref "Z1")
      (value "PGB1010603")
      (footprint "eagle-import:SPARKFUN-RESISTORS_0603-RES")
      (fields (field (name "MF") "Littelfuse") (field (name "MPN") "PGB1010603NRHF"))
      (libsource (lib "eagle-import") (part "SPARKFUN-RESISTORS_RESISTOR0603-RES"))
    )
    (comp (ref "Z2")
      (value "PGB1010603")
      (footprint "eagle-import:SPARKFUN-RESISTORS_0603-RES")
      (fields (field (name "MF") "Littelfuse") (field (name "MPN") "PGB1010603NRHF"))
      (libsource (lib "eagle-import") (part "SPARKFUN-RESISTORS_RESISTOR0603-RES"))
    )
    (comp (ref "Z3")
      (value "PGB1010603")
      (footprint "eagle-import:SPARKFUN-RESISTORS_0603-RES")
      (fields (field (name "MF") "Littelfuse") (field (name "MPN") "PGB1010603NRHF"))
      (libsource (lib "eagle-import") (part "SPARKFUN-RESISTORS_RESISTOR0603-RES"))
    )
  )
  (nets
    (net (code "1") (name "+3V3") (class "Default")
      (node (ref "C14") (pin "1") (pinfunction "1_1") (pintype "passive"))
      (node (ref "C15") (pin "1") (pinfunction "1_1") (pintype "passive"))
      (node (ref "C6") (pin "1") (pinfunction "1_1") (pintype "passive"))
      (node (ref "R12") (pin "2") (pinfunction "2_2") (pintype "passive"))
      (node (ref "R17") (pin "2") (pinfunction "2_2") (pintype "passive"))
      (node (ref "R18") (pin "2") (pinfunction "2_2") (pintype "passive"))
      (node (ref "R23") (pin "2") (pinfunction "2_2") (pintype "passive"))
      (node (ref "R26") (pin "2") (pinfunction "2_2") (pintype "passive"))
      (node (ref "R27") (pin "2") (pinfunction "2_2") (pintype "passive"))
      (node (ref "R28") (pin "2") (pinfunction "2_2") (pintype "passive"))
      (node (ref "U$10") (pin "1") (pinfunction "P$1_1") (pintype "bidirectional"))
      (node (ref "U5") (pin "5") (pinfunction "OUT_5") (pintype "passive"))
      (node (ref "U6") (pin "3V3") (pinfunction "3V3_3V3") (pintype "bidirectional"))
      (node (ref "U8") (pin "P$1") (pinfunction "VDD_P$1") (pintype "bidirectional"))
      (node (ref "U8") (pin "P$8") (pinfunction "VDDIO_P$8") (pintype "bidirectional"))
    )
    (net (code "2") (name "+5V") (class "Default")
      (node (ref "C18") (pin "1") (pinfunction "1_1") (pintype "passive"))
      (node (ref "C4") (pin "1") (pinfunction "1_1") (pintype "passive"))
      (node (ref "C8") (pin "1") (pinfunction "1_1") (pintype "passive"))
      (node (ref "SW1") (pin "P0") (pinfunction "P_P0") (pintype "passive"))
      (node (ref "SW1") (pin "P1") (pinfunction "P_P1") (pintype "passive"))
      (node (ref "TP7") (pin "TP") (pinfunction "TP_TP") (pintype "input"))
      (node (ref "U1") (pin "6") (pinfunction "VREGIN_6") (pintype "bidirectional"))
      (node (ref "U10") (pin "1") (pinfunction "S_1") (pintype "passive"))
      (node (ref "U10") (pin "4") (pinfunction "S_4") (pintype "passive"))
      (node (ref "U11") (pin "1") (pinfunction "S_1") (pintype "passive"))
      (node (ref "U11") (pin "4") (pinfunction "S_4") (pintype "passive"))
      (node (ref "U12") (pin "1") (pinfunction "S_1") (pintype "passive"))
      (node (ref "U12") (pin "4") (pinfunction "S_4") (pintype "passive"))
      (node (ref "U3") (pin "16") (pinfunction "VCC_16") (pintype "power_in"))
      (node (ref "U5") (pin "1") (pinfunction "IN_1") (pintype "input"))
      (node (ref "U5") (pin "3") (pinfunction "EN_3") (pintype "input"))
      (node (ref "U9") (pin "1") (pinfunction "S_1") (pintype "passive"))
      (node (ref "U9") (pin "4") (pinfunction "S_4") (pintype "passive"))
    )
    (net (code "3") (name "1ROW0") (class "Default")
      (node (ref "LED_1") (pin "2") (pinfunction "VCC_2") (pintype "bidirectional"))
      (node (ref "LED_2") (pin "2") (pinfunction "VCC_2") (pintype "bidirectional"))
      (node (ref "LED_3") (pin "2") (pinfunction "VCC_2") (pintype "bidirectional"))
      (node (ref "LED_4") (pin "2") (pinfunction "VCC_2") (pintype "bidirectional"))
      (node (ref "LED_5") (pin "2") (pinfunction "VCC_2") (pintype "bidirectional"))
      (node (ref "LED_6") (pin "2") (pinfunction "VCC_2") (pintype "bidirectional"))
      (node (ref "LED_7") (pin "2") (pinfunction "VCC_2") (pintype "bidirectional"))
      (node (ref "LED_8") (pin "2") (pinfunction "VCC_2") (pintype "bidirectional"))
      (node (ref "R2") (pin "2") (pinfunction "2_2") (pintype "passive"))
      (node (ref "U10") (pin "6") (pinfunction "D_6") (pintype "passive"))
    )
    (net (code "4") (name "1ROW1") (class "Default")
      (node (ref "LED_10") (pin "2") (pinfunction "VCC_2") (pintype "bidirectional"))
      (node (ref "LED_11") (pin "2") (pinfunction "VCC_2") (pintype "bidirectional"))
      (node (ref "LED_12") (pin "2") (pinfunction "VCC_2") (pintype "bidirectional"))
      (node (ref "LED_13") (pin "2") (pinfunction "VCC_2") (pintype "bidirectional"))
      (node (ref "LED_14") (pin "2") (pinfunction "VCC_2") (pintype "bidirectional"))
      (node (ref "LED_15") (pin "2") (pinfunction "VCC_2") (pintype "bidirectional"))
      (node (ref "LED_16") (pin "2") (pinfunction "VCC_2") (pintype "bidirectional"))
      (node (ref "LED_9") (pin "2") (pinfunction "VCC_2") (pintype "bidirectional"))
      (node (ref "R3") (pin "2") (pinfunction "2_2") (pintype "passive"))
      (node (ref "U10") (pin "3") (pinfunction "D_3") (pintype "passive"))
    )
    (net (code "5") (name "1ROW2") (class "Default")
      (node (ref "LED_17") (pin "2") (pinfunction "VCC_2") (pintype "bidirectional"))
      (node (ref "LED_18") (pin "2") (pinfunction "VCC_2") (pintype "bidirectional"))
      (node (ref "LED_19") (pin "2") (pinfunction "VCC_2") (pintype "bidirectional"))
      (node (ref "LED_20") (pin "2") (pinfunction "VCC_2") (pintype "bidirectional"))
      (node (ref "LED_21") (pin "2") (pinfunction "VCC_2") (pintype "bidirectional"))
      (node (ref "LED_22") (pin "2") (pinfunction "VCC_2") (pintype "bidirectional"))
      (node (ref "LED_23") (pin "2") (pinfunction "VCC_2") (pintype "bidirectional"))
      (node (ref "LED_24") (pin "2") (pinfunction "VCC_2") (pintype "bidirectional"))
      (node (ref "R4") (pin "2") (pinfunction "2_2") (pintype "passive"))
      (node (ref "U9") (pin "6") (pinfunction "D_6") (pintype "passive"))
    )
    (net (code "6") (name "1ROW3") (class "Default")
      (node (ref "LED_25") (pin "2") (pinfunction "VCC_2") (pintype "bidirectional"))
      (node (ref "LED_26") (pin "2") (pinfunction "VCC_2") (pintype "bidirectional"))
      (node (ref "LED_27") (pin "2") (pinfunction "VCC_2") (pintype "bidirectional"))
      (node (ref "LED_28") (pin "2") (pinfunction "VCC_2") (pintype "bidirectional"))
      (node (ref "LED_29") (pin "2") (pinfunction "VCC_2") (pintype "bidirectional"))
      (node (ref "LED_30") (pin "2") (pinfunction "VCC_2") (pintype "bidirectional"))
      (node (ref "LED_31") (pin "2") (pinfunction "VCC_2") (pintype "bidirectional"))
      (node (ref "LED_32") (pin "2") (pinfunction "VCC_2") (pintype "bidirectional"))
      (node (ref "R5") (pin "2") (pinfunction "2_2") (pintype "passive"))
      (node (ref "U9") (pin "3") (pinfunction "D_3") (pintype "passive"))
    )
    (net (code "7") (name "1ROW4") (class "Default")
      (node (ref "LED_33") (pin "2") (pinfunction "VCC_2") (pintype "bidirectional"))
      (node (ref "LED_34") (pin "2") (pinfunction "VCC_2") (pintype "bidirectional"))
      (node (ref "LED_35") (pin "2") (pinfunction "VCC_2") (pintype "bidirectional"))
      (node (ref "LED_36") (pin "2") (pinfunction "VCC_2") (pintype "bidirectional"))
      (node (ref "LED_37") (pin "2") (pinfunction "VCC_2") (pintype "bidirectional"))
      (node (ref "LED_38") (pin "2") (pinfunction "VCC_2") (pintype "bidirectional"))
      (node (ref "LED_39") (pin "2") (pinfunction "VCC_2") (pintype "bidirectional"))
      (node (ref "LED_40") (pin "2") (pinfunction "VCC_2") (pintype "bidirectional"))
      (node (ref "R13") (pin "2") (pinfunction "2_2") (pintype "passive"))
      (node (ref "U11") (pin "6") (pinfunction "D_6") (pintype "passive"))
    )
    (net (code "8") (name "1ROW5") (class "Default")
      (node (ref "LED_41") (pin "2") (pinfunction "VCC_2") (pintype "bidirectional"))
      (node (ref "LED_42") (pin "2") (pinfunction "VCC_2") (pintype "bidirectional"))
      (node (ref "LED_43") (pin "2") (pinfunction "VCC_2") (pintype "bidirectional"))
      (node (ref "LED_44") (pin "2") (pinfunction "VCC_2") (pintype "bidirectional"))
      (node (ref "LED_45") (pin "2") (pinfunction "VCC_2") (pintype "bidirectional"))
      (node (ref "LED_46") (pin "2") (pinfunction "VCC_2") (pintype "bidirectional"))
      (node (ref "LED_47") (pin "2") (pinfunction "VCC_2") (pintype "bidirectional"))
      (node (ref "LED_48") (pin "2") (pinfunction "VCC_2") (pintype "bidirectional"))
      (node (ref "R14") (pin "2") (pinfunction "2_2") (pintype "passive"))
      (node (ref "U11") (pin "3") (pinfunction "D_3") (pintype "passive"))
    )
    (net (code "9") (name "1ROW6") (class "Default")
      (node (ref "LED_49") (pin "2") (pinfunction "VCC_2") (pintype "bidirectional"))
      (node (ref "LED_50") (pin "2") (pinfunction "VCC_2") (pintype "bidirectional"))
      (node (ref "LED_51") (pin "2") (pinfunction "VCC_2") (pintype "bidirectional"))
      (node (ref "LED_52") (pin "2") (pinfunction "VCC_2") (pintype "bidirectional"))
      (node (ref "LED_53") (pin "2") (pinfunction "VCC_2") (pintype "bidirectional"))
      (node (ref "LED_54") (pin "2") (pinfunction "VCC_2") (pintype "bidirectional"))
      (node (ref "LED_55") (pin "2") (pinfunction "VCC_2") (pintype "bidirectional"))
      (node (ref "LED_56") (pin "2") (pinfunction "VCC_2") (pintype "bidirectional"))
      (node (ref "R15") (pin "2") (pinfunction "2_2") (pintype "passive"))
      (node (ref "U12") (pin "6") (pinfunction "D_6") (pintype "passive"))
    )
    (net (code "10") (name "1ROW7") (class "Default")
      (node (ref "LED_57") (pin "2") (pinfunction "VCC_2") (pintype "bidirectional"))
      (node (ref "LED_58") (pin "2") (pinfunction "VCC_2") (pintype "bidirectional"))
      (node (ref "LED_59") (pin "2") (pinfunction "VCC_2") (pintype "bidirectional"))
      (node (ref "LED_60") (pin "2") (pinfunction "VCC_2") (pintype "bidirectional"))
      (node (ref "LED_61") (pin "2") (pinfunction "VCC_2") (pintype "bidirectional"))
      (node (ref "LED_62") (pin "2") (pinfunction "VCC_2") (pintype "bidirectional"))
      (node (ref "LED_63") (pin "2") (pinfunction "VCC_2") (pintype "bidirectional"))
      (node (ref "LED_64") (pin "2") (pinfunction "VCC_2") (pintype "bidirectional"))
      (node (ref "R16") (pin "2") (pinfunction "2_2") (pintype "passive"))
      (node (ref "U12") (pin "3") (pinfunction "D_3") (pintype "passive"))
    )
    (net (code "11") (name "ACC_INT1") (class "Default")
      (node (ref "U6") (pin "IO13") (pinfunction "IO13_IO13") (pintype "bidirectional"))
      (node (ref "U8") (pin "P$3") (pinfunction "INT1_P$3") (pintype "bidirectional"))
    )
    (net (code "12") (name "ARM_3V3") (class "Default")
      (node (ref "C1") (pin "1") (pinfunction "1_1") (pintype "passive"))
      (node (ref "C11") (pin "1") (pinfunction "1_1") (pintype "passive"))
      (node (ref "C2") (pin "1") (pinfunction "1_1") (pintype "passive"))
      (node (ref "C3") (pin "1") (pinfunction "1_1") (pintype "passive"))
      (node (ref "C5") (pin "1") (pinfunction "1_1") (pintype "passive"))
      (node (ref "C7") (pin "1") (pinfunction "1_1") (pintype "passive"))
      (node (ref "R6") (pin "2") (pinfunction "2_2") (pintype "passive"))
      (node (ref "TP9") (pin "TP") (pinfunction "TP_TP") (pintype "input"))
      (node (ref "U1") (pin "1") (pinfunction "VDD_1") (pintype "bidirectional"))
      (node (ref "U1") (pin "11") (pinfunction "VBAT_11") (pintype "bidirectional"))
      (node (ref "U1") (pin "5") (pinfunction "VOUT33_5") (pintype "bidirectional"))
      (node (ref "U1") (pin "7") (pinfunction "VDDA_7") (pintype "bidirectional"))
      (node (ref "U2") (pin "24") (pinfunction "VCC_24") (pintype "bidirectional"))
      (node (ref "U4") (pin "24") (pinfunction "VCC_24") (pintype "bidirectional"))
    )
    (net (code "13") (name "ARM_BOOTLOADER") (class "Default")
      (node (ref "TP16") (pin "TP") (pinfunction "TP_TP") (pintype "input"))
      (node (ref "U1") (pin "25") (pinfunction "PTC4_25") (pintype "bidirectional"))
    )
    (net (code "14") (name "ARM_RESET") (class "Default")
      (node (ref "TP14") (pin "TP") (pinfunction "TP_TP") (pintype "input"))
      (node (ref "U1") (pin "19") (pinfunction "RESET_B_19") (pintype "bidirectional"))
    )
    (net (code "15") (name "ARM_RX") (class "Default")
      (node (ref "TP13") (pin "TP") (pinfunction "TP_TP") (pintype "input"))
      (node (ref "U1") (pin "13") (pinfunction "PTA1_13") (pintype "bidirectional"))
      (node (ref "U6") (pin "TXD") (pinfunction "TXD_TXD") (pintype "bidirectional"))
    )
    (net (code "16") (name "ARM_RX1") (class "Default")
      (node (ref "R12") (pin "1") (pinfunction "1_1") (pintype "passive"))
      (node (ref "TP23") (pin "TP") (pinfunction "TP_TP") (pintype "input"))
      (node (ref "U1") (pin "24") (pinfunction "PTC3_24") (pintype "bidirectional"))
      (node (ref "U6") (pin "IO2") (pinfunction "IO2_IO2") (pintype "bidirectional"))
    )
    (net (code "17") (name "ARM_TCK") (class "Default")
      (node (ref "TP11") (pin "TP") (pinfunction "TP_TP") (pintype "input"))
      (node (ref "U1") (pin "12") (pinfunction "PTA0_12") (pintype "bidirectional"))
    )
    (net (code "18") (name "ARM_TMS") (class "Default")
      (node (ref "TP10") (pin "TP") (pinfunction "TP_TP") (pintype "input"))
      (node (ref "U1") (pin "15") (pinfunction "PTA3_15") (pintype "bidirectional"))
    )
    (net (code "19") (name "ARM_TX") (class "Default")
      (node (ref "TP12") (pin "TP") (pinfunction "TP_TP") (pintype "input"))
      (node (ref "U1") (pin "14") (pinfunction "PTA2_14") (pintype "bidirectional"))
      (node (ref "U6") (pin "RXD") (pinfunction "RXD_RXD") (pintype "bidirectional"))
    )
    (net (code "20") (name "BCOL0") (class "Default")
      (node (ref "LED_1") (pin "3") (pinfunction "BLUE_3") (pintype "bidirectional"))
      (node (ref "LED_17") (pin "3") (pinfunction "BLUE_3") (pintype "bidirectional"))
      (node (ref "LED_25") (pin "3") (pinfunction "BLUE_3") (pintype "bidirectional"))
      (node (ref "LED_33") (pin "3") (pinfunction "BLUE_3") (pintype "bidirectional"))
      (node (ref "LED_41") (pin "3") (pinfunction "BLUE_3") (pintype "bidirectional"))
      (node (ref "LED_49") (pin "3") (pinfunction "BLUE_3") (pintype "bidirectional"))
      (node (ref "LED_57") (pin "3") (pinfunction "BLUE_3") (pintype "bidirectional"))
      (node (ref "LED_9") (pin "3") (pinfunction "BLUE_3") (pintype "bidirectional"))
      (node (ref "U2") (pin "13") (pinfunction "OUT8_13") (pintype "bidirectional"))
    )
    (net (code "21") (name "BCOL1") (class "Default")
      (node (ref "LED_10") (pin "3") (pinfunction "BLUE_3") (pintype "bidirectional"))
      (node (ref "LED_18") (pin "3") (pinfunction "BLUE_3") (pintype "bidirectional"))
      (node (ref "LED_2") (pin "3") (pinfunction "BLUE_3") (pintype "bidirectional"))
      (node (ref "LED_26") (pin "3") (pinfunction "BLUE_3") (pintype "bidirectional"))
      (node (ref "LED_34") (pin "3") (pinfunction "BLUE_3") (pintype "bidirectional"))
      (node (ref "LED_42") (pin "3") (pinfunction "BLUE_3") (pintype "bidirectional"))
      (node (ref "LED_50") (pin "3") (pinfunction "BLUE_3") (pintype "bidirectional"))
      (node (ref "LED_58") (pin "3") (pinfunction "BLUE_3") (pintype "bidirectional"))
      (node (ref "U2") (pin "14") (pinfunction "OUT9_14") (pintype "bidirectional"))
    )
    (net (code "22") (name "BCOL2") (class "Default")
      (node (ref "LED_11") (pin "3") (pinfunction "BLUE_3") (pintype "bidirectional"))
      (node (ref "LED_19") (pin "3") (pinfunction "BLUE_3") (pintype "bidirectional"))
      (node (ref "LED_27") (pin "3") (pinfunction "BLUE_3") (pintype "bidirectional"))
      (node (ref "LED_3") (pin "3") (pinfunction "BLUE_3") (pintype "bidirectional"))
      (node (ref "LED_35") (pin "3") (pinfunction "BLUE_3") (pintype "bidirectional"))
      (node (ref "LED_43") (pin "3") (pinfunction "BLUE_3") (pintype "bidirectional"))
      (node (ref "LED_51") (pin "3") (pinfunction "BLUE_3") (pintype "bidirectional"))
      (node (ref "LED_59") (pin "3") (pinfunction "BLUE_3") (pintype "bidirectional"))
      (node (ref "U2") (pin "15") (pinfunction "OUT10_15") (pintype "bidirectional"))
    )
    (net (code "23") (name "BCOL3") (class "Default")
      (node (ref "LED_12") (pin "3") (pinfunction "BLUE_3") (pintype "bidirectional"))
      (node (ref "LED_20") (pin "3") (pinfunction "BLUE_3") (pintype "bidirectional"))
      (node (ref "LED_28") (pin "3") (pinfunction "BLUE_3") (pintype "bidirectional"))
      (node (ref "LED_36") (pin "3") (pinfunction "BLUE_3") (pintype "bidirectional"))
      (node (ref "LED_4") (pin "3") (pinfunction "BLUE_3") (pintype "bidirectional"))
      (node (ref "LED_44") (pin "3") (pinfunction "BLUE_3") (pintype "bidirectional"))
      (node (ref "LED_52") (pin "3") (pinfunction "BLUE_3") (pintype "bidirectional"))
      (node (ref "LED_60") (pin "3") (pinfunction "BLUE_3") (pintype "bidirectional"))
      (node (ref "U2") (pin "16") (pinfunction "OUT11_16") (pintype "bidirectional"))
    )
    (net (code "24") (name "BCOL4") (class "Default")
      (node (ref "LED_13") (pin "3") (pinfunction "BLUE_3") (pintype "bidirectional"))
      (node (ref "LED_21") (pin "3") (pinfunction "BLUE_3") (pintype "bidirectional"))
      (node (ref "LED_29") (pin "3") (pinfunction "BLUE_3") (pintype "bidirectional"))
      (node (ref "LED_37") (pin "3") (pinfunction "BLUE_3") (pintype "bidirectional"))
      (node (ref "LED_45") (pin "3") (pinfunction "BLUE_3") (pintype "bidirectional"))
      (node (ref "LED_5") (pin "3") (pinfunction "BLUE_3") (pintype "bidirectional"))
      (node (ref "LED_53") (pin "3") (pinfunction "BLUE_3") (pintype "bidirectional"))
      (node (ref "LED_61") (pin "3") (pinfunction "BLUE_3") (pintype "bidirectional"))
      (node (ref "U2") (pin "17") (pinfunction "OUT12_17") (pintype "bidirectional"))
    )
    (net (code "25") (name "BCOL5") (class "Default")
      (node (ref "LED_14") (pin "3") (pinfunction "BLUE_3") (pintype "bidirectional"))
      (node (ref "LED_22") (pin "3") (pinfunction "BLUE_3") (pintype "bidirectional"))
      (node (ref "LED_30") (pin "3") (pinfunction "BLUE_3") (pintype "bidirectional"))
      (node (ref "LED_38") (pin "3") (pinfunction "BLUE_3") (pintype "bidirectional"))
      (node (ref "LED_46") (pin "3") (pinfunction "BLUE_3") (pintype "bidirectional"))
      (node (ref "LED_54") (pin "3") (pinfunction "BLUE_3") (pintype "bidirectional"))
      (node (ref "LED_6") (pin "3") (pinfunction "BLUE_3") (pintype "bidirectional"))
      (node (ref "LED_62") (pin "3") (pinfunction "BLUE_3") (pintype "bidirectional"))
      (node (ref "U2") (pin "18") (pinfunction "OUT13_18") (pintype "bidirectional"))
    )
    (net (code "26") (name "BCOL6") (class "Default")
      (node (ref "LED_15") (pin "3") (pinfunction "BLUE_3") (pintype "bidirectional"))
      (node (ref "LED_23") (pin "3") (pinfunction "BLUE_3") (pintype "bidirectional"))
      (node (ref "LED_31") (pin "3") (pinfunction "BLUE_3") (pintype "bidirectional"))
      (node (ref "LED_39") (pin "3") (pinfunction "BLUE_3") (pintype "bidirectional"))
      (node (ref "LED_47") (pin "3") (pinfunction "BLUE_3") (pintype "bidirectional"))
      (node (ref "LED_55") (pin "3") (pinfunction "BLUE_3") (pintype "bidirectional"))
      (node (ref "LED_63") (pin "3") (pinfunction "BLUE_3") (pintype "bidirectional"))
      (node (ref "LED_7") (pin "3") (pinfunction "BLUE_3") (pintype "bidirectional"))
      (node (ref "U2") (pin "19") (pinfunction "OUT14_19") (pintype "bidirectional"))
    )
    (net (code "27") (name "BCOL7") (class "Default")
      (node (ref "LED_16") (pin "3") (pinfunction "BLUE_3") (pintype "bidirectional"))
      (node (ref "LED_24") (pin "3") (pinfunction "BLUE_3") (pintype "bidirectional"))
      (node (ref "LED_32") (pin "3") (pinfunction "BLUE_3") (pintype "bidirectional"))
      (node (ref "LED_40") (pin "3") (pinfunction "BLUE_3") (pintype "bidirectional"))
      (node (ref "LED_48") (pin "3") (pinfunction "BLUE_3") (pintype "bidirectional"))
      (node (ref "LED_56") (pin "3") (pinfunction "BLUE_3") (pintype "bidirectional"))
      (node (ref "LED_64") (pin "3") (pinfunction "BLUE_3") (pintype "bidirectional"))
      (node (ref "LED_8") (pin "3") (pinfunction "BLUE_3") (pintype "bidirectional"))
      (node (ref "U2") (pin "20") (pinfunction "OUT15_20") (pintype "bidirectional"))
    )
    (net (code "28") (name "BOOST_5V") (class "Default")
      (node (ref "C9") (pin "1") (pinfunction "1_1") (pintype "passive"))
      (node (ref "D2") (pin "A") (pinfunction "A_A") (pintype "passive"))
      (node (ref "TP24") (pin "TP") (pinfunction "TP_TP") (pintype "input"))
      (node (ref "U7") (pin "8") (pinfunction "OUT_8") (pintype "bidirectional"))
    )
    (net (code "29") (name "BUTTON") (class "Default")
      (node (ref "R28") (pin "1") (pinfunction "1_1") (pintype "passive"))
      (node (ref "SW2") (pin "1") (pinfunction "P_1") (pintype "passive"))
      (node (ref "SW2") (pin "2") (pinfunction "P_2") (pintype "passive"))
      (node (ref "TP25") (pin "TP") (pinfunction "TP_TP") (pintype "input"))
      (node (ref "U6") (pin "IO4") (pinfunction "IO4_IO4") (pintype "bidirectional"))
    )
    (net (code "30") (name "CHARGE") (class "Default")
      (node (ref "D1") (pin "A") (pinfunction "A_A") (pintype "passive"))
      (node (ref "U7") (pin "6") (pinfunction "LED2_6") (pintype "bidirectional"))
    )
    (net (code "31") (name "DISCHARGE") (class "Default")
      (node (ref "D4") (pin "A") (pinfunction "A_A") (pintype "passive"))
      (node (ref "U7") (pin "5") (pinfunction "LED1_5") (pintype "bidirectional"))
    )
    (net (code "32") (name "ESP_GPIO0") (class "Default")
      (node (ref "R23") (pin "1") (pinfunction "1_1") (pintype "passive"))
      (node (ref "TP15") (pin "TP") (pinfunction "TP_TP") (pintype "input"))
      (node (ref "U1") (pin "21") (pinfunction "PTB1_21") (pintype "bidirectional"))
      (node (ref "U6") (pin "IO0") (pinfunction "IO0_IO0") (pintype "bidirectional"))
    )
    (net (code "33") (name "ESP_GPIO15") (class "Default")
      (node (ref "R25") (pin "2") (pinfunction "2_2") (pintype "passive"))
      (node (ref "U6") (pin "IO15") (pinfunction "IO15_IO15") (pintype "bidirectional"))
    )
    (net (code "34") (name "ESP_GPIO16") (class "Default")
      (node (ref "U$9") (pin "1") (pinfunction "P$1_1") (pintype "bidirectional"))
      (node (ref "U6") (pin "IO18") (pinfunction "IO16_IO18") (pintype "bidirectional"))
    )
    (net (code "35") (name "ESP_RESET") (class "Default")
      (node (ref "R27") (pin "1") (pinfunction "1_1") (pintype "passive"))
      (node (ref "TP17") (pin "TP") (pinfunction "TP_TP") (pintype "input"))
      (node (ref "U1") (pin "20") (pinfunction "PTB0_20") (pintype "bidirectional"))
      (node (ref "U6") (pin "RST") (pinfunction "RST_RST") (pintype "bidirectional"))
    )
    (net (code "36") (name "ESP_TOUT") (class "Default")
      (node (ref "U6") (pin "TOUT") (pinfunction "TOUT_TOUT") (pintype "bidirectional"))
    )
    (net (code "37") (name "EXP_GPIO5") (class "Default")
      (node (ref "U$6") (pin "1") (pinfunction "P$1_1") (pintype "bidirectional"))
      (node (ref "U6") (pin "IO5") (pinfunction "IO5_IO5") (pintype "bidirectional"))
    )
    (net (code "38") (name "GCOL0") (class "Default")
      (node (ref "LED_1") (pin "4") (pinfunction "GREEN_4") (pintype "bidirectional"))
      (node (ref "LED_17") (pin "4") (pinfunction "GREEN_4") (pintype "bidirectional"))
      (node (ref "LED_25") (pin "4") (pinfunction "GREEN_4") (pintype "bidirectional"))
      (node (ref "LED_33") (pin "4") (pinfunction "GREEN_4") (pintype "bidirectional"))
      (node (ref "LED_41") (pin "4") (pinfunction "GREEN_4") (pintype "bidirectional"))
      (node (ref "LED_49") (pin "4") (pinfunction "GREEN_4") (pintype "bidirectional"))
      (node (ref "LED_57") (pin "4") (pinfunction "GREEN_4") (pintype "bidirectional"))
      (node (ref "LED_9") (pin "4") (pinfunction "GREEN_4") (pintype "bidirectional"))
      (node (ref "U4") (pin "5") (pinfunction "OUT0_5") (pintype "bidirectional"))
    )
    (net (code "39") (name "GCOL1") (class "Default")
      (node (ref "LED_10") (pin "4") (pinfunction "GREEN_4") (pintype "bidirectional"))
      (node (ref "LED_18") (pin "4") (pinfunction "GREEN_4") (pintype "bidirectional"))
      (node (ref "LED_2") (pin "4") (pinfunction "GREEN_4") (pintype "bidirectional"))
      (node (ref "LED_26") (pin "4") (pinfunction "GREEN_4") (pintype "bidirectional"))
      (node (ref "LED_34") (pin "4") (pinfunction "GREEN_4") (pintype "bidirectional"))
      (node (ref "LED_42") (pin "4") (pinfunction "GREEN_4") (pintype "bidirectional"))
      (node (ref "LED_50") (pin "4") (pinfunction "GREEN_4") (pintype "bidirectional"))
      (node (ref "LED_58") (pin "4") (pinfunction "GREEN_4") (pintype "bidirectional"))
      (node (ref "U4") (pin "6") (pinfunction "OUT1_6") (pintype "bidirectional"))
    )
    (net (code "40") (name "GCOL2") (class "Default")
      (node (ref "LED_11") (pin "4") (pinfunction "GREEN_4") (pintype "bidirectional"))
      (node (ref "LED_19") (pin "4") (pinfunction "GREEN_4") (pintype "bidirectional"))
      (node (ref "LED_27") (pin "4") (pinfunction "GREEN_4") (pintype "bidirectional"))
      (node (ref "LED_3") (pin "4") (pinfunction "GREEN_4") (pintype "bidirectional"))
      (node (ref "LED_35") (pin "4") (pinfunction "GREEN_4") (pintype "bidirectional"))
      (node (ref "LED_43") (pin "4") (pinfunction "GREEN_4") (pintype "bidirectional"))
      (node (ref "LED_51") (pin "4") (pinfunction "GREEN_4") (pintype "bidirectional"))
      (node (ref "LED_59") (pin "4") (pinfunction "GREEN_4") (pintype "bidirectional"))
      (node (ref "U4") (pin "7") (pinfunction "OUT2_7") (pintype "bidirectional"))
    )
    (net (code "41") (name "GCOL3") (class "Default")
      (node (ref "LED_12") (pin "4") (pinfunction "GREEN_4") (pintype "bidirectional"))
      (node (ref "LED_20") (pin "4") (pinfunction "GREEN_4") (pintype "bidirectional"))
      (node (ref "LED_28") (pin "4") (pinfunction "GREEN_4") (pintype "bidirectional"))
      (node (ref "LED_36") (pin "4") (pinfunction "GREEN_4") (pintype "bidirectional"))
      (node (ref "LED_4") (pin "4") (pinfunction "GREEN_4") (pintype "bidirectional"))
      (node (ref "LED_44") (pin "4") (pinfunction "GREEN_4") (pintype "bidirectional"))
      (node (ref "LED_52") (pin "4") (pinfunction "GREEN_4") (pintype "bidirectional"))
      (node (ref "LED_60") (pin "4") (pinfunction "GREEN_4") (pintype "bidirectional"))
      (node (ref "U4") (pin "8") (pinfunction "OUT3_8") (pintype "bidirectional"))
    )
    (net (code "42") (name "GCOL4") (class "Default")
      (node (ref "LED_13") (pin "4") (pinfunction "GREEN_4") (pintype "bidirectional"))
      (node (ref "LED_21") (pin "4") (pinfunction "GREEN_4") (pintype "bidirectional"))
      (node (ref "LED_29") (pin "4") (pinfunction "GREEN_4") (pintype "bidirectional"))
      (node (ref "LED_37") (pin "4") (pinfunction "GREEN_4") (pintype "bidirectional"))
      (node (ref "LED_45") (pin "4") (pinfunction "GREEN_4") (pintype "bidirectional"))
      (node (ref "LED_5") (pin "4") (pinfunction "GREEN_4") (pintype "bidirectional"))
      (node (ref "LED_53") (pin "4") (pinfunction "GREEN_4") (pintype "bidirectional"))
      (node (ref "LED_61") (pin "4") (pinfunction "GREEN_4") (pintype "bidirectional"))
      (node (ref "U4") (pin "9") (pinfunction "OUT4_9") (pintype "bidirectional"))
    )
    (net (code "43") (name "GCOL5") (class "Default")
      (node (ref "LED_14") (pin "4") (pinfunction "GREEN_4") (pintype "bidirectional"))
      (node (ref "LED_22") (pin "4") (pinfunction "GREEN_4") (pintype "bidirectional"))
      (node (ref "LED_30") (pin "4") (pinfunction "GREEN_4") (pintype "bidirectional"))
      (node (ref "LED_38") (pin "4") (pinfunction "GREEN_4") (pintype "bidirectional"))
      (node (ref "LED_46") (pin "4") (pinfunction "GREEN_4") (pintype "bidirectional"))
      (node (ref "LED_54") (pin "4") (pinfunction "GREEN_4") (pintype "bidirectional"))
      (node (ref "LED_6") (pin "4") (pinfunction "GREEN_4") (pintype "bidirectional"))
      (node (ref "LED_62") (pin "4") (pinfunction "GREEN_4") (pintype "bidirectional"))
      (node (ref "U4") (pin "10") (pinfunction "OUT5_10") (pintype "bidirectional"))
    )
    (net (code "44") (name "GCOL6") (class "Default")
      (node (ref "LED_15") (pin "4") (pinfunction "GREEN_4") (pintype "bidirectional"))
      (node (ref "LED_23") (pin "4") (pinfunction "GREEN_4") (pintype "bidirectional"))
      (node (ref "LED_31") (pin "4") (pinfunction "GREEN_4") (pintype "bidirectional"))
      (node (ref "LED_39") (pin "4") (pinfunction "GREEN_4") (pintype "bidirectional"))
      (node (ref "LED_47") (pin "4") (pinfunction "GREEN_4") (pintype "bidirectional"))
      (node (ref "LED_55") (pin "4") (pinfunction "GREEN_4") (pintype "bidirectional"))
      (node (ref "LED_63") (pin "4") (pinfunction "GREEN_4") (pintype "bidirectional"))
      (node (ref "LED_7") (pin "4") (pinfunction "GREEN_4") (pintype "bidirectional"))
      (node (ref "U4") (pin "11") (pinfunction "OUT6_11") (pintype "bidirectional"))
    )
    (net (code "45") (name "GCOL7") (class "Default")
      (node (ref "LED_16") (pin "4") (pinfunction "GREEN_4") (pintype "bidirectional"))
      (node (ref "LED_24") (pin "4") (pinfunction "GREEN_4") (pintype "bidirectional"))
      (node (ref "LED_32") (pin "4") (pinfunction "GREEN_4") (pintype "bidirectional"))
      (node (ref "LED_40") (pin "4") (pinfunction "GREEN_4") (pintype "bidirectional"))
      (node (ref "LED_48") (pin "4") (pinfunction "GREEN_4") (pintype "bidirectional"))
      (node (ref "LED_56") (pin "4") (pinfunction "GREEN_4") (pintype "bidirectional"))
      (node (ref "LED_64") (pin "4") (pinfunction "GREEN_4") (pintype "bidirectional"))
      (node (ref "LED_8") (pin "4") (pinfunction "GREEN_4") (pintype "bidirectional"))
      (node (ref "U4") (pin "12") (pinfunction "OUT7_12") (pintype "bidirectional"))
    )
    (net (code "46") (name "GND") (class "Default")
      (node (ref "C1") (pin "2") (pinfunction "2_2") (pintype "passive"))
      (node (ref "C10") (pin "2") (pinfunction "2_2") (pintype "passive"))
      (node (ref "C11") (pin "2") (pinfunction "2_2") (pintype "passive"))
      (node (ref "C12") (pin "2") (pinfunction "2_2") (pintype "passive"))
      (node (ref "C13") (pin "2") (pinfunction "2_2") (pintype "passive"))
      (node (ref "C14") (pin "2") (pinfunction "2_2") (pintype "passive"))
      (node (ref "C15") (pin "2") (pinfunction "2_2") (pintype "passive"))
      (node (ref "C16") (pin "2") (pinfunction "2_2") (pintype "passive"))
      (node (ref "C17") (pin "2") (pinfunction "2_2") (pintype "passive"))
      (node (ref "C18") (pin "2") (pinfunction "2_2") (pintype "passive"))
      (node (ref "C2") (pin "2") (pinfunction "2_2") (pintype "passive"))
      (node (ref "C3") (pin "2") (pinfunction "2_2") (pintype "passive"))
      (node (ref "C4") (pin "2") (pinfunction "2_2") (pintype "passive"))
      (node (ref "C5") (pin "2") (pinfunction "2_2") (pintype "passive"))
      (node (ref "C6") (pin "2") (pinfunction "2_2") (pintype "passive"))
      (node (ref "C7") (pin "2") (pinfunction "2_2") (pintype "passive"))
      (node (ref "C8") (pin "2") (pinfunction "2_2") (pintype "passive"))
      (node (ref "C9") (pin "2") (pinfunction "2_2") (pintype "passive"))
      (node (ref "D5") (pin "A") (pinfunction "A_A") (pintype "passive"))
      (node (ref "J1") (pin "PAD$1") (pinfunction "SHIELD_PAD$1") (pintype "bidirectional"))
      (node (ref "J1") (pin "PAD$10") (pinfunction "SHIELD_PAD$10") (pintype "bidirectional"))
      (node (ref "J1") (pin "PAD$2") (pinfunction "SHIELD_PAD$2") (pintype "bidirectional"))
      (node (ref "J1") (pin "PAD$3") (pinfunction "SHIELD_PAD$3") (pintype "bidirectional"))
      (node (ref "J1") (pin "PAD$4") (pinfunction "SHIELD_PAD$4") (pintype "bidirectional"))
      (node (ref "J1") (pin "PAD$5") (pinfunction "SHIELD_PAD$5") (pintype "bidirectional"))
      (node (ref "J1") (pin "PAD$6") (pinfunction "SHIELD_PAD$6") (pintype "bidirectional"))
      (node (ref "J1") (pin "PAD$7") (pinfunction "SHIELD_PAD$7") (pintype "bidirectional"))
      (node (ref "J1") (pin "PAD$8") (pinfunction "SHIELD_PAD$8") (pintype "bidirectional"))
      (node (ref "J1") (pin "PAD$9") (pinfunction "SHIELD_PAD$9") (pintype "bidirectional"))
      (node (ref "J1") (pin "PIN$5") (pinfunction "GND_PIN$5") (pintype "bidirectional"))
      (node (ref "J2") (pin "-") (pinfunction "-_-") (pintype "bidirectional"))
      (node (ref "Q1") (pin "P$2") (pinfunction "P$1_P$2") (pintype "bidirectional"))
      (node (ref "Q1") (pin "P$4") (pinfunction "P$1_P$4") (pintype "bidirectional"))
      (node (ref "R1") (pin "1") (pinfunction "1_1") (pintype "passive"))
      (node (ref "R11") (pin "1") (pinfunction "1_1") (pintype "passive"))
      (node (ref "R13") (pin "1") (pinfunction "1_1") (pintype "passive"))
      (node (ref "R14") (pin "1") (pinfunction "1_1") (pintype "passive"))
      (node (ref "R15") (pin "1") (pinfunction "1_1") (pintype "passive"))
      (node (ref "R16") (pin "1") (pinfunction "1_1") (pintype "passive"))
      (node (ref "R2") (pin "1") (pinfunction "1_1") (pintype "passive"))
      (node (ref "R21") (pin "1") (pinfunction "1_1") (pintype "passive"))
      (node (ref "R24") (pin "1") (pinfunction "1_1") (pintype "passive"))
      (node (ref "R25") (pin "1") (pinfunction "1_1") (pintype "passive"))
      (node (ref "R3") (pin "1") (pinfunction "1_1") (pintype "passive"))
      (node (ref "R4") (pin "1") (pinfunction "1_1") (pintype "passive"))
      (node (ref "R5") (pin "1") (pinfunction "1_1") (pintype "passive"))
      (node (ref "R9") (pin "1") (pinfunction "1_1") (pintype "passive"))
      (node (ref "SJ1") (pin "1") (pinfunction "1_1") (pintype "passive"))
      (node (ref "SW2") (pin "3") (pinfunction "S_3") (pintype "passive"))
      (node (ref "SW2") (pin "4") (pinfunction "S_4") (pintype "passive"))
      (node (ref "SW2") (pin "5") (pinfunction "SHIELD_5") (pintype "passive"))
      (node (ref "TP18") (pin "TP") (pinfunction "TP_TP") (pintype "input"))
      (node (ref "U$2") (pin "1") (pinfunction "P$1_1") (pintype "bidirectional"))
      (node (ref "U1") (pin "2") (pinfunction "VSS_2") (pintype "bidirectional"))
      (node (ref "U1") (pin "8") (pinfunction "VSSA_8") (pintype "bidirectional"))
      (node (ref "U1") (pin "PAD@1") (pinfunction "VSS_PAD@1") (pintype "bidirectional"))
      (node (ref "U1") (pin "PAD@11") (pinfunction "VSS_PAD@11") (pintype "bidirectional"))
      (node (ref "U1") (pin "PAD@4") (pinfunction "VSS_PAD@4") (pintype "bidirectional"))
      (node (ref "U1") (pin "PAD@9") (pinfunction "VSS_PAD@9") (pintype "bidirectional"))
      (node (ref "U2") (pin "1") (pinfunction "GND_1") (pintype "bidirectional"))
      (node (ref "U3") (pin "5") (pinfunction "G2B_5") (pintype "input"))
      (node (ref "U3") (pin "8") (pinfunction "GND_8") (pintype "power_in"))
      (node (ref "U4") (pin "1") (pinfunction "GND_1") (pintype "bidirectional"))
      (node (ref "U5") (pin "2") (pinfunction "GND_2") (pintype "input"))
      (node (ref "U6") (pin "GND$1") (pinfunction "GND_GND$1") (pintype "bidirectional"))
      (node (ref "U6") (pin "GND$2") (pinfunction "GND_GND$2") (pintype "bidirectional"))
      (node (ref "U6") (pin "GND$3") (pinfunction "GND_GND$3") (pintype "bidirectional"))
      (node (ref "U7") (pin "2") (pinfunction "PGND_2") (pintype "bidirectional"))
      (node (ref "U7") (pin "7") (pinfunction "GND_7") (pintype "bidirectional"))
      (node (ref "U8") (pin "P$6") (pinfunction "GND_P$6") (pintype "bidirectional"))
      (node (ref "U8") (pin "P$7") (pinfunction "GND_P$7") (pintype "bidirectional"))
      (node (ref "U8") (pin "P$9") (pinfunction "GND_P$9") (pintype "bidirectional"))
      (node (ref "Z1") (pin "1") (pinfunction "1_1") (pintype "passive"))
      (node (ref "Z2") (pin "1") (pinfunction "1_1") (pintype "passive"))
      (node (ref "Z3") (pin "1") (pinfunction "1_1") (pintype "passive"))
    )
    (net (code "47") (name "I2C_SCL") (class "Default")
      (node (ref "R18") (pin "1") (pinfunction "1_1") (pintype "passive"))
      (node (ref "TP6") (pin "TP") (pinfunction "TP_TP") (pintype "input"))
      (node (ref "U6") (pin "IO14") (pinfunction "IO14_IO14") (pintype "bidirectional"))
      (node (ref "U8") (pin "P$2") (pinfunction "SCL_P$2") (pintype "bidirectional"))
    )
    (net (code "48") (name "I2C_SDA") (class "Default")
      (node (ref "R17") (pin "1") (pinfunction "1_1") (pintype "passive"))
      (node (ref "TP5") (pin "TP") (pinfunction "TP_TP") (pintype "input"))
      (node (ref "U6") (pin "IO12") (pinfunction "IO12_IO12") (pintype "bidirectional"))
      (node (ref "U8") (pin "P$10") (pinfunction "SDA_P$10") (pintype "bidirectional"))
    )
    (net (code "49") (name "LED_CLK") (class "Default")
      (node (ref "TP2") (pin "TP") (pinfunction "TP_TP") (pintype "input"))
      (node (ref "U1") (pin "26") (pinfunction "PTC5_26") (pintype "bidirectional"))
      (node (ref "U2") (pin "3") (pinfunction "CLK_3") (pintype "bidirectional"))
      (node (ref "U4") (pin "3") (pinfunction "CLK_3") (pintype "bidirectional"))
    )
    (net (code "50") (name "LED_DAT_0") (class "Default")
      (node (ref "TP1") (pin "TP") (pinfunction "TP_TP") (pintype "input"))
      (node (ref "U1") (pin "27") (pinfunction "PTC6_27") (pintype "bidirectional"))
      (node (ref "U2") (pin "2") (pinfunction "DIN_2") (pintype "bidirectional"))
    )
    (net (code "51") (name "LED_DAT_1") (class "Default")
      (node (ref "U2") (pin "22") (pinfunction "DOUT_22") (pintype "bidirectional"))
      (node (ref "U4") (pin "2") (pinfunction "DIN_2") (pintype "bidirectional"))
    )
    (net (code "52") (name "LED_HS_EN") (class "Default")
      (node (ref "R21") (pin "2") (pinfunction "2_2") (pintype "passive"))
      (node (ref "TP22") (pin "TP") (pinfunction "TP_TP") (pintype "input"))
      (node (ref "U1") (pin "22") (pinfunction "PTC1_22") (pintype "bidirectional"))
      (node (ref "U3") (pin "6") (pinfunction "G1_6") (pintype "input"))
    )
    (net (code "53") (name "LED_OE") (class "Default")
      (node (ref "R6") (pin "1") (pinfunction "1_1") (pintype "passive"))
      (node (ref "TP4") (pin "TP") (pinfunction "TP_TP") (pintype "input"))
      (node (ref "U1") (pin "16") (pinfunction "PTA4_16") (pintype "bidirectional"))
      (node (ref "U2") (pin "21") (pinfunction "OE_21") (pintype "bidirectional"))
      (node (ref "U3") (pin "4") (pinfunction "G2A_4") (pintype "input"))
      (node (ref "U4") (pin "21") (pinfunction "OE_21") (pintype "bidirectional"))
    )
    (net (code "54") (name "LED_ROW_A") (class "Default")
      (node (ref "TP19") (pin "TP") (pinfunction "TP_TP") (pintype "input"))
      (node (ref "U1") (pin "30") (pinfunction "PTD5_30") (pintype "bidirectional"))
      (node (ref "U3") (pin "1") (pinfunction "A_1") (pintype "input"))
    )
    (net (code "55") (name "LED_ROW_B") (class "Default")
      (node (ref "TP20") (pin "TP") (pinfunction "TP_TP") (pintype "input"))
      (node (ref "U1") (pin "31") (pinfunction "PTD6_31") (pintype "bidirectional"))
      (node (ref "U3") (pin "2") (pinfunction "B_2") (pintype "input"))
    )
    (net (code "56") (name "LED_ROW_C") (class "Default")
      (node (ref "TP21") (pin "TP") (pinfunction "TP_TP") (pintype "input"))
      (node (ref "U1") (pin "32") (pinfunction "PTD7_32") (pintype "bidirectional"))
      (node (ref "U3") (pin "3") (pinfunction "C_3") (pintype "input"))
    )
    (net (code "57") (name "LED_S0") (class "Default")
      (node (ref "U10") (pin "2") (pinfunction "G_2") (pintype "passive"))
      (node (ref "U3") (pin "15") (pinfunction "Y0_15") (pintype "output"))
    )
    (net (code "58") (name "LED_S1") (class "Default")
      (node (ref "U10") (pin "5") (pinfunction "G_5") (pintype "passive"))
      (node (ref "U3") (pin "14") (pinfunction "Y1_14") (pintype "output"))
    )
    (net (code "59") (name "LED_S2") (class "Default")
      (node (ref "U3") (pin "13") (pinfunction "Y2_13") (pintype "output"))
      (node (ref "U9") (pin "2") (pinfunction "G_2") (pintype "passive"))
    )
    (net (code "60") (name "LED_S3") (class "Default")
      (node (ref "U3") (pin "12") (pinfunction "Y3_12") (pintype "output"))
      (node (ref "U9") (pin "5") (pinfunction "G_5") (pintype "passive"))
    )
    (net (code "61") (name "LED_S4") (class "Default")
      (node (ref "U11") (pin "2") (pinfunction "G_2") (pintype "passive"))
      (node (ref "U3") (pin "11") (pinfunction "Y4_11") (pintype "output"))
    )
    (net (code "62") (name "LED_S5") (class "Default")
      (node (ref "U11") (pin "5") (pinfunction "G_5") (pintype "passive"))
      (node (ref "U3") (pin "10") (pinfunction "Y5_10") (pintype "output"))
    )
    (net (code "63") (name "LED_S6") (class "Default")
      (node (ref "U12") (pin "2") (pinfunction "G_2") (pintype "passive"))
      (node (ref "U3") (pin "9") (pinfunction "Y6_9") (pintype "output"))
    )
    (net (code "64") (name "LED_S7") (class "Default")
      (node (ref "U12") (pin "5") (pinfunction "G_5") (pintype "passive"))
      (node (ref "U3") (pin "7") (pinfunction "Y7_7") (pintype "output"))
    )
    (net (code "65") (name "LED_STB") (class "Default")
      (node (ref "TP3") (pin "TP") (pinfunction "TP_TP") (pintype "input"))
      (node (ref "U1") (pin "29") (pinfunction "PTD4_29") (pintype "bidirectional"))
      (node (ref "U2") (pin "4") (pinfunction "LATCH_4") (pintype "bidirectional"))
      (node (ref "U4") (pin "4") (pinfunction "LATCH_4") (pintype "bidirectional"))
    )
    (net (code "66") (name "Net-(C10-Pad1)") (class "Default")
      (node (ref "C10") (pin "1") (pinfunction "1_1") (pintype "passive"))
      (node (ref "R10") (pin "2") (pinfunction "2_2") (pintype "passive"))
    )
    (net (code "67") (name "Net-(D1-PadC)") (class "Default")
      (node (ref "D1") (pin "C") (pinfunction "C_C") (pintype "passive"))
      (node (ref "D4") (pin "C") (pinfunction "C_C") (pintype "passive"))
      (node (ref "SJ1") (pin "2") (pinfunction "2_2") (pintype "passive"))
    )
    (net (code "68") (name "Net-(D2-PadC)") (class "Default")
      (node (ref "D2") (pin "C") (pinfunction "C_C") (pintype "passive"))
      (node (ref "D3") (pin "C") (pinfunction "C_C") (pintype "passive"))
      (node (ref "SW1") (pin "S0") (pinfunction "S_S0") (pintype "passive"))
      (node (ref "SW1") (pin "S1") (pinfunction "S_S1") (pintype "passive"))
    )
    (net (code "69") (name "Net-(J1-D+)") (class "Default")
      (node (ref "J1") (pin "PIN$3") (pinfunction "D+_PIN$3") (pintype "bidirectional"))
      (node (ref "R8") (pin "1") (pinfunction "1_1") (pintype "passive"))
      (node (ref "Z2") (pin "2") (pinfunction "2_2") (pintype "passive"))
    )
    (net (code "70") (name "Net-(J1-D-)") (class "Default")
      (node (ref "J1") (pin "PIN$2") (pinfunction "D-_PIN$2") (pintype "bidirectional"))
      (node (ref "R7") (pin "1") (pinfunction "1_1") (pintype "passive"))
      (node (ref "Z1") (pin "2") (pinfunction "2_2") (pintype "passive"))
    )
    (net (code "71") (name "Net-(L1-2)") (class "Default")
      (node (ref "L1") (pin "P$2") (pinfunction "2_P$2") (pintype "passive"))
      (node (ref "R10") (pin "1") (pinfunction "1_1") (pintype "passive"))
      (node (ref "U7") (pin "1") (pinfunction "LX_1") (pintype "bidirectional"))
    )
    (net (code "72") (name "Net-(Q1-1)") (class "Default")
      (node (ref "Q1") (pin "P$1") (pinfunction "1_P$1") (pintype "passive"))
      (node (ref "U1") (pin "18") (pinfunction "PTA19_18") (pintype "bidirectional"))
    )
    (net (code "73") (name "Net-(Q1-2)") (class "Default")
      (node (ref "Q1") (pin "P$3") (pinfunction "2_P$3") (pintype "passive"))
      (node (ref "U1") (pin "17") (pinfunction "PTA18_17") (pintype "bidirectional"))
    )
    (net (code "74") (name "Net-(R11-Pad2)") (class "Default")
      (node (ref "R11") (pin "2") (pinfunction "2_2") (pintype "passive"))
      (node (ref "SW1") (pin "O0") (pinfunction "O_O0") (pintype "passive"))
      (node (ref "SW1") (pin "O1") (pinfunction "O_O1") (pintype "passive"))
    )
    (net (code "75") (name "Net-(R19B-1)") (class "Default")
      (node (ref "R19") (pin "2") (pinfunction "1_2") (pintype "passive"))
      (node (ref "U2") (pin "7") (pinfunction "OUT2_7") (pintype "bidirectional"))
    )
    (net (code "76") (name "Net-(R19C-1)") (class "Default")
      (node (ref "R19") (pin "3") (pinfunction "1_3") (pintype "passive"))
      (node (ref "U2") (pin "6") (pinfunction "OUT1_6") (pintype "bidirectional"))
    )
    (net (code "77") (name "Net-(R19D-1)") (class "Default")
      (node (ref "R19") (pin "4") (pinfunction "1_4") (pintype "passive"))
      (node (ref "U2") (pin "5") (pinfunction "OUT0_5") (pintype "bidirectional"))
    )
    (net (code "78") (name "Net-(R20B-1)") (class "Default")
      (node (ref "R20") (pin "2") (pinfunction "1_2") (pintype "passive"))
      (node (ref "U2") (pin "11") (pinfunction "OUT6_11") (pintype "bidirectional"))
    )
    (net (code "79") (name "Net-(R20C-1)") (class "Default")
      (node (ref "R20") (pin "3") (pinfunction "1_3") (pintype "passive"))
      (node (ref "U2") (pin "10") (pinfunction "OUT5_10") (pintype "bidirectional"))
    )
    (net (code "80") (name "Net-(R20D-1)") (class "Default")
      (node (ref "R20") (pin "4") (pinfunction "1_4") (pintype "passive"))
      (node (ref "U2") (pin "9") (pinfunction "OUT4_9") (pintype "bidirectional"))
    )
    (net (code "81") (name "Net-(R26-Pad1)") (class "Default")
      (node (ref "R26") (pin "1") (pinfunction "1_1") (pintype "passive"))
      (node (ref "U6") (pin "EN") (pinfunction "EN_EN") (pintype "bidirectional"))
    )
    (net (code "82") (name "Net-(U2-CREF)") (class "Default")
      (node (ref "R1") (pin "2") (pinfunction "2_2") (pintype "passive"))
      (node (ref "U2") (pin "23") (pinfunction "CREF_23") (pintype "bidirectional"))
    )
    (net (code "83") (name "Net-(U2-OUT3)") (class "Default")
      (node (ref "R19") (pin "1") (pinfunction "1_1") (pintype "passive"))
      (node (ref "U2") (pin "8") (pinfunction "OUT3_8") (pintype "bidirectional"))
    )
    (net (code "84") (name "Net-(U2-OUT7)") (class "Default")
      (node (ref "R20") (pin "1") (pinfunction "1_1") (pintype "passive"))
      (node (ref "U2") (pin "12") (pinfunction "OUT7_12") (pintype "bidirectional"))
    )
    (net (code "85") (name "Net-(U4-CREF)") (class "Default")
      (node (ref "R9") (pin "2") (pinfunction "2_2") (pintype "passive"))
      (node (ref "U4") (pin "23") (pinfunction "CREF_23") (pintype "bidirectional"))
    )
    (net (code "86") (name "Net-(U5-BP)") (class "Default")
      (node (ref "C16") (pin "1") (pinfunction "1_1") (pintype "passive"))
      (node (ref "U5") (pin "4") (pinfunction "BP_4") (pintype "input"))
    )
    (net (code "87") (name "Net-(U8-BYP)") (class "Default")
      (node (ref "C13") (pin "1") (pinfunction "1_1") (pintype "passive"))
      (node (ref "U8") (pin "P$4") (pinfunction "BYP_P$4") (pintype "bidirectional"))
    )
    (net (code "88") (name "RCOL0") (class "Default")
      (node (ref "LED_1") (pin "1") (pinfunction "RED_1") (pintype "bidirectional"))
      (node (ref "LED_17") (pin "1") (pinfunction "RED_1") (pintype "bidirectional"))
      (node (ref "LED_25") (pin "1") (pinfunction "RED_1") (pintype "bidirectional"))
      (node (ref "LED_33") (pin "1") (pinfunction "RED_1") (pintype "bidirectional"))
      (node (ref "LED_41") (pin "1") (pinfunction "RED_1") (pintype "bidirectional"))
      (node (ref "LED_49") (pin "1") (pinfunction "RED_1") (pintype "bidirectional"))
      (node (ref "LED_57") (pin "1") (pinfunction "RED_1") (pintype "bidirectional"))
      (node (ref "LED_9") (pin "1") (pinfunction "RED_1") (pintype "bidirectional"))
      (node (ref "R19") (pin "5") (pinfunction "2_5") (pintype "passive"))
    )
    (net (code "89") (name "RCOL1") (class "Default")
      (node (ref "LED_10") (pin "1") (pinfunction "RED_1") (pintype "bidirectional"))
      (node (ref "LED_18") (pin "1") (pinfunction "RED_1") (pintype "bidirectional"))
      (node (ref "LED_2") (pin "1") (pinfunction "RED_1") (pintype "bidirectional"))
      (node (ref "LED_26") (pin "1") (pinfunction "RED_1") (pintype "bidirectional"))
      (node (ref "LED_34") (pin "1") (pinfunction "RED_1") (pintype "bidirectional"))
      (node (ref "LED_42") (pin "1") (pinfunction "RED_1") (pintype "bidirectional"))
      (node (ref "LED_50") (pin "1") (pinfunction "RED_1") (pintype "bidirectional"))
      (node (ref "LED_58") (pin "1") (pinfunction "RED_1") (pintype "bidirectional"))
      (node (ref "R19") (pin "6") (pinfunction "2_6") (pintype "passive"))
    )
    (net (code "90") (name "RCOL2") (class "Default")
      (node (ref "LED_11") (pin "1") (pinfunction "RED_1") (pintype "bidirectional"))
      (node (ref "LED_19") (pin "1") (pinfunction "RED_1") (pintype "bidirectional"))
      (node (ref "LED_27") (pin "1") (pinfunction "RED_1") (pintype "bidirectional"))
      (node (ref "LED_3") (pin "1") (pinfunction "RED_1") (pintype "bidirectional"))
      (node (ref "LED_35") (pin "1") (pinfunction "RED_1") (pintype "bidirectional"))
      (node (ref "LED_43") (pin "1") (pinfunction "RED_1") (pintype "bidirectional"))
      (node (ref "LED_51") (pin "1") (pinfunction "RED_1") (pintype "bidirectional"))
      (node (ref "LED_59") (pin "1") (pinfunction "RED_1") (pintype "bidirectional"))
      (node (ref "R19") (pin "7") (pinfunction "2_7") (pintype "passive"))
    )
    (net (code "91") (name "RCOL3") (class "Default")
      (node (ref "LED_12") (pin "1") (pinfunction "RED_1") (pintype "bidirectional"))
      (node (ref "LED_20") (pin "1") (pinfunction "RED_1") (pintype "bidirectional"))
      (node (ref "LED_28") (pin "1") (pinfunction "RED_1") (pintype "bidirectional"))
      (node (ref "LED_36") (pin "1") (pinfunction "RED_1") (pintype "bidirectional"))
      (node (ref "LED_4") (pin "1") (pinfunction "RED_1") (pintype "bidirectional"))
      (node (ref "LED_44") (pin "1") (pinfunction "RED_1") (pintype "bidirectional"))
      (node (ref "LED_52") (pin "1") (pinfunction "RED_1") (pintype "bidirectional"))
      (node (ref "LED_60") (pin "1") (pinfunction "RED_1") (pintype "bidirectional"))
      (node (ref "R19") (pin "8") (pinfunction "2_8") (pintype "passive"))
    )
    (net (code "92") (name "RCOL4") (class "Default")
      (node (ref "LED_13") (pin "1") (pinfunction "RED_1") (pintype "bidirectional"))
      (node (ref "LED_21") (pin "1") (pinfunction "RED_1") (pintype "bidirectional"))
      (node (ref "LED_29") (pin "1") (pinfunction "RED_1") (pintype "bidirectional"))
      (node (ref "LED_37") (pin "1") (pinfunction "RED_1") (pintype "bidirectional"))
      (node (ref "LED_45") (pin "1") (pinfunction "RED_1") (pintype "bidirectional"))
      (node (ref "LED_5") (pin "1") (pinfunction "RED_1") (pintype "bidirectional"))
      (node (ref "LED_53") (pin "1") (pinfunction "RED_1") (pintype "bidirectional"))
      (node (ref "LED_61") (pin "1") (pinfunction "RED_1") (pintype "bidirectional"))
      (node (ref "R20") (pin "5") (pinfunction "2_5") (pintype "passive"))
    )
    (net (code "93") (name "RCOL5") (class "Default")
      (node (ref "LED_14") (pin "1") (pinfunction "RED_1") (pintype "bidirectional"))
      (node (ref "LED_22") (pin "1") (pinfunction "RED_1") (pintype "bidirectional"))
      (node (ref "LED_30") (pin "1") (pinfunction "RED_1") (pintype "bidirectional"))
      (node (ref "LED_38") (pin "1") (pinfunction "RED_1") (pintype "bidirectional"))
      (node (ref "LED_46") (pin "1") (pinfunction "RED_1") (pintype "bidirectional"))
      (node (ref "LED_54") (pin "1") (pinfunction "RED_1") (pintype "bidirectional"))
      (node (ref "LED_6") (pin "1") (pinfunction "RED_1") (pintype "bidirectional"))
      (node (ref "LED_62") (pin "1") (pinfunction "RED_1") (pintype "bidirectional"))
      (node (ref "R20") (pin "6") (pinfunction "2_6") (pintype "passive"))
    )
    (net (code "94") (name "RCOL6") (class "Default")
      (node (ref "LED_15") (pin "1") (pinfunction "RED_1") (pintype "bidirectional"))
      (node (ref "LED_23") (pin "1") (pinfunction "RED_1") (pintype "bidirectional"))
      (node (ref "LED_31") (pin "1") (pinfunction "RED_1") (pintype "bidirectional"))
      (node (ref "LED_39") (pin "1") (pinfunction "RED_1") (pintype "bidirectional"))
      (node (ref "LED_47") (pin "1") (pinfunction "RED_1") (pintype "bidirectional"))
      (node (ref "LED_55") (pin "1") (pinfunction "RED_1") (pintype "bidirectional"))
      (node (ref "LED_63") (pin "1") (pinfunction "RED_1") (pintype "bidirectional"))
      (node (ref "LED_7") (pin "1") (pinfunction "RED_1") (pintype "bidirectional"))
      (node (ref "R20") (pin "7") (pinfunction "2_7") (pintype "passive"))
    )
    (net (code "95") (name "RCOL7") (class "Default")
      (node (ref "LED_16") (pin "1") (pinfunction "RED_1") (pintype "bidirectional"))
      (node (ref "LED_24") (pin "1") (pinfunction "RED_1") (pintype "bidirectional"))
      (node (ref "LED_32") (pin "1") (pinfunction "RED_1") (pintype "bidirectional"))
      (node (ref "LED_40") (pin "1") (pinfunction "RED_1") (pintype "bidirectional"))
      (node (ref "LED_48") (pin "1") (pinfunction "RED_1") (pintype "bidirectional"))
      (node (ref "LED_56") (pin "1") (pinfunction "RED_1") (pintype "bidirectional"))
      (node (ref "LED_64") (pin "1") (pinfunction "RED_1") (pintype "bidirectional"))
      (node (ref "LED_8") (pin "1") (pinfunction "RED_1") (pintype "bidirectional"))
      (node (ref "R20") (pin "8") (pinfunction "2_8") (pintype "passive"))
    )
    (net (code "96") (name "USB_5V") (class "Default")
      (node (ref "C17") (pin "1") (pinfunction "1_1") (pintype "passive"))
      (node (ref "D3") (pin "A") (pinfunction "A_A") (pintype "passive"))
      (node (ref "J1") (pin "PIN$1") (pinfunction "VCC_PIN$1") (pintype "bidirectional"))
      (node (ref "R24") (pin "2") (pinfunction "2_2") (pintype "passive"))
      (node (ref "U7") (pin "4") (pinfunction "VCC_4") (pintype "bidirectional"))
      (node (ref "Z3") (pin "2") (pinfunction "2_2") (pintype "passive"))
    )
    (net (code "97") (name "USB_D+") (class "Default")
      (node (ref "R8") (pin "2") (pinfunction "2_2") (pintype "passive"))
      (node (ref "U1") (pin "3") (pinfunction "USB0_DP_3") (pintype "bidirectional"))
    )
    (net (code "98") (name "USB_D-") (class "Default")
      (node (ref "R7") (pin "2") (pinfunction "2_2") (pintype "passive"))
      (node (ref "U1") (pin "4") (pinfunction "USB0_DM_4") (pintype "bidirectional"))
    )
    (net (code "99") (name "VBAT") (class "Default")
      (node (ref "J2") (pin "+") (pinfunction "+_+") (pintype "bidirectional"))
      (node (ref "L2") (pin "1") (pinfunction "1_1") (pintype "passive"))
    )
    (net (code "100") (name "VBAT_FUSED") (class "Default")
      (node (ref "C12") (pin "1") (pinfunction "1_1") (pintype "passive"))
      (node (ref "D5") (pin "C") (pinfunction "C_C") (pintype "passive"))
      (node (ref "L1") (pin "P$1") (pinfunction "1_P$1") (pintype "passive"))
      (node (ref "L2") (pin "2") (pinfunction "2_2") (pintype "passive"))
      (node (ref "TP8") (pin "TP") (pinfunction "TP_TP") (pintype "input"))
      (node (ref "U7") (pin "3") (pinfunction "BAT_3") (pintype "bidirectional"))
    )
    (net (code "101") (name "unconnected-(J1-ID-PadPIN$4)") (class "Default")
      (node (ref "J1") (pin "PIN$4") (pinfunction "ID_PIN$4") (pintype "bidirectional"))
    )
    (net (code "102") (name "unconnected-(U1-EXTAL32-Pad10)") (class "Default")
      (node (ref "U1") (pin "10") (pinfunction "EXTAL32_10") (pintype "bidirectional"))
    )
    (net (code "103") (name "unconnected-(U1-PTC2-Pad23)") (class "Default")
      (node (ref "U1") (pin "23") (pinfunction "PTC2_23") (pintype "bidirectional"))
    )
    (net (code "104") (name "unconnected-(U1-PTC7-Pad28)") (class "Default")
      (node (ref "U1") (pin "28") (pinfunction "PTC7_28") (pintype "bidirectional"))
    )
    (net (code "105") (name "unconnected-(U1-XTAL32-Pad9)") (class "Default")
      (node (ref "U1") (pin "9") (pinfunction "XTAL32_9") (pintype "bidirectional"))
    )
    (net (code "106") (name "unconnected-(U4-DOUT-Pad22)") (class "Default")
      (node (ref "U4") (pin "22") (pinfunction "DOUT_22") (pintype "bidirectional"))
    )
    (net (code "107") (name "unconnected-(U4-OUT8-Pad13)") (class "Default")
      (node (ref "U4") (pin "13") (pinfunction "OUT8_13") (pintype "bidirectional"))
    )
    (net (code "108") (name "unconnected-(U4-OUT9-Pad14)") (class "Default")
      (node (ref "U4") (pin "14") (pinfunction "OUT9_14") (pintype "bidirectional"))
    )
    (net (code "109") (name "unconnected-(U4-OUT10-Pad15)") (class "Default")
      (node (ref "U4") (pin "15") (pinfunction "OUT10_15") (pintype "bidirectional"))
    )
    (net (code "110") (name "unconnected-(U4-OUT11-Pad16)") (class "Default")
      (node (ref "U4") (pin "16") (pinfunction "OUT11_16") (pintype "bidirectional"))
    )
    (net (code "111") (name "unconnected-(U4-OUT12-Pad17)") (class "Default")
      (node (ref "U4") (pin "17") (pinfunction "OUT12_17") (pintype "bidirectional"))
    )
    (net (code "112") (name "unconnected-(U4-OUT13-Pad18)") (class "Default")
      (node (ref "U4") (pin "18") (pinfunction "OUT13_18") (pintype "bidirectional"))
    )
    (net (code "113") (name "unconnected-(U4-OUT14-Pad19)") (class "Default")
      (node (ref "U4") (pin "19") (pinfunction "OUT14_19") (pintype "bidirectional"))
    )
    (net (code "114") (name "unconnected-(U4-OUT15-Pad20)") (class "Default")
      (node (ref "U4") (pin "20") (pinfunction "OUT15_20") (pintype "bidirectional"))
    )
    (net (code "115") (name "unconnected-(U8-INT2-PadP$5)") (class "Default")
      (node (ref "U8") (pin "P$5") (pinfunction "INT2_P$5") (pintype "bidirectional"))
    )
  )
)
